# twoBandRepeater.net
KiCad netlist of a schematic drawn in EAGLE
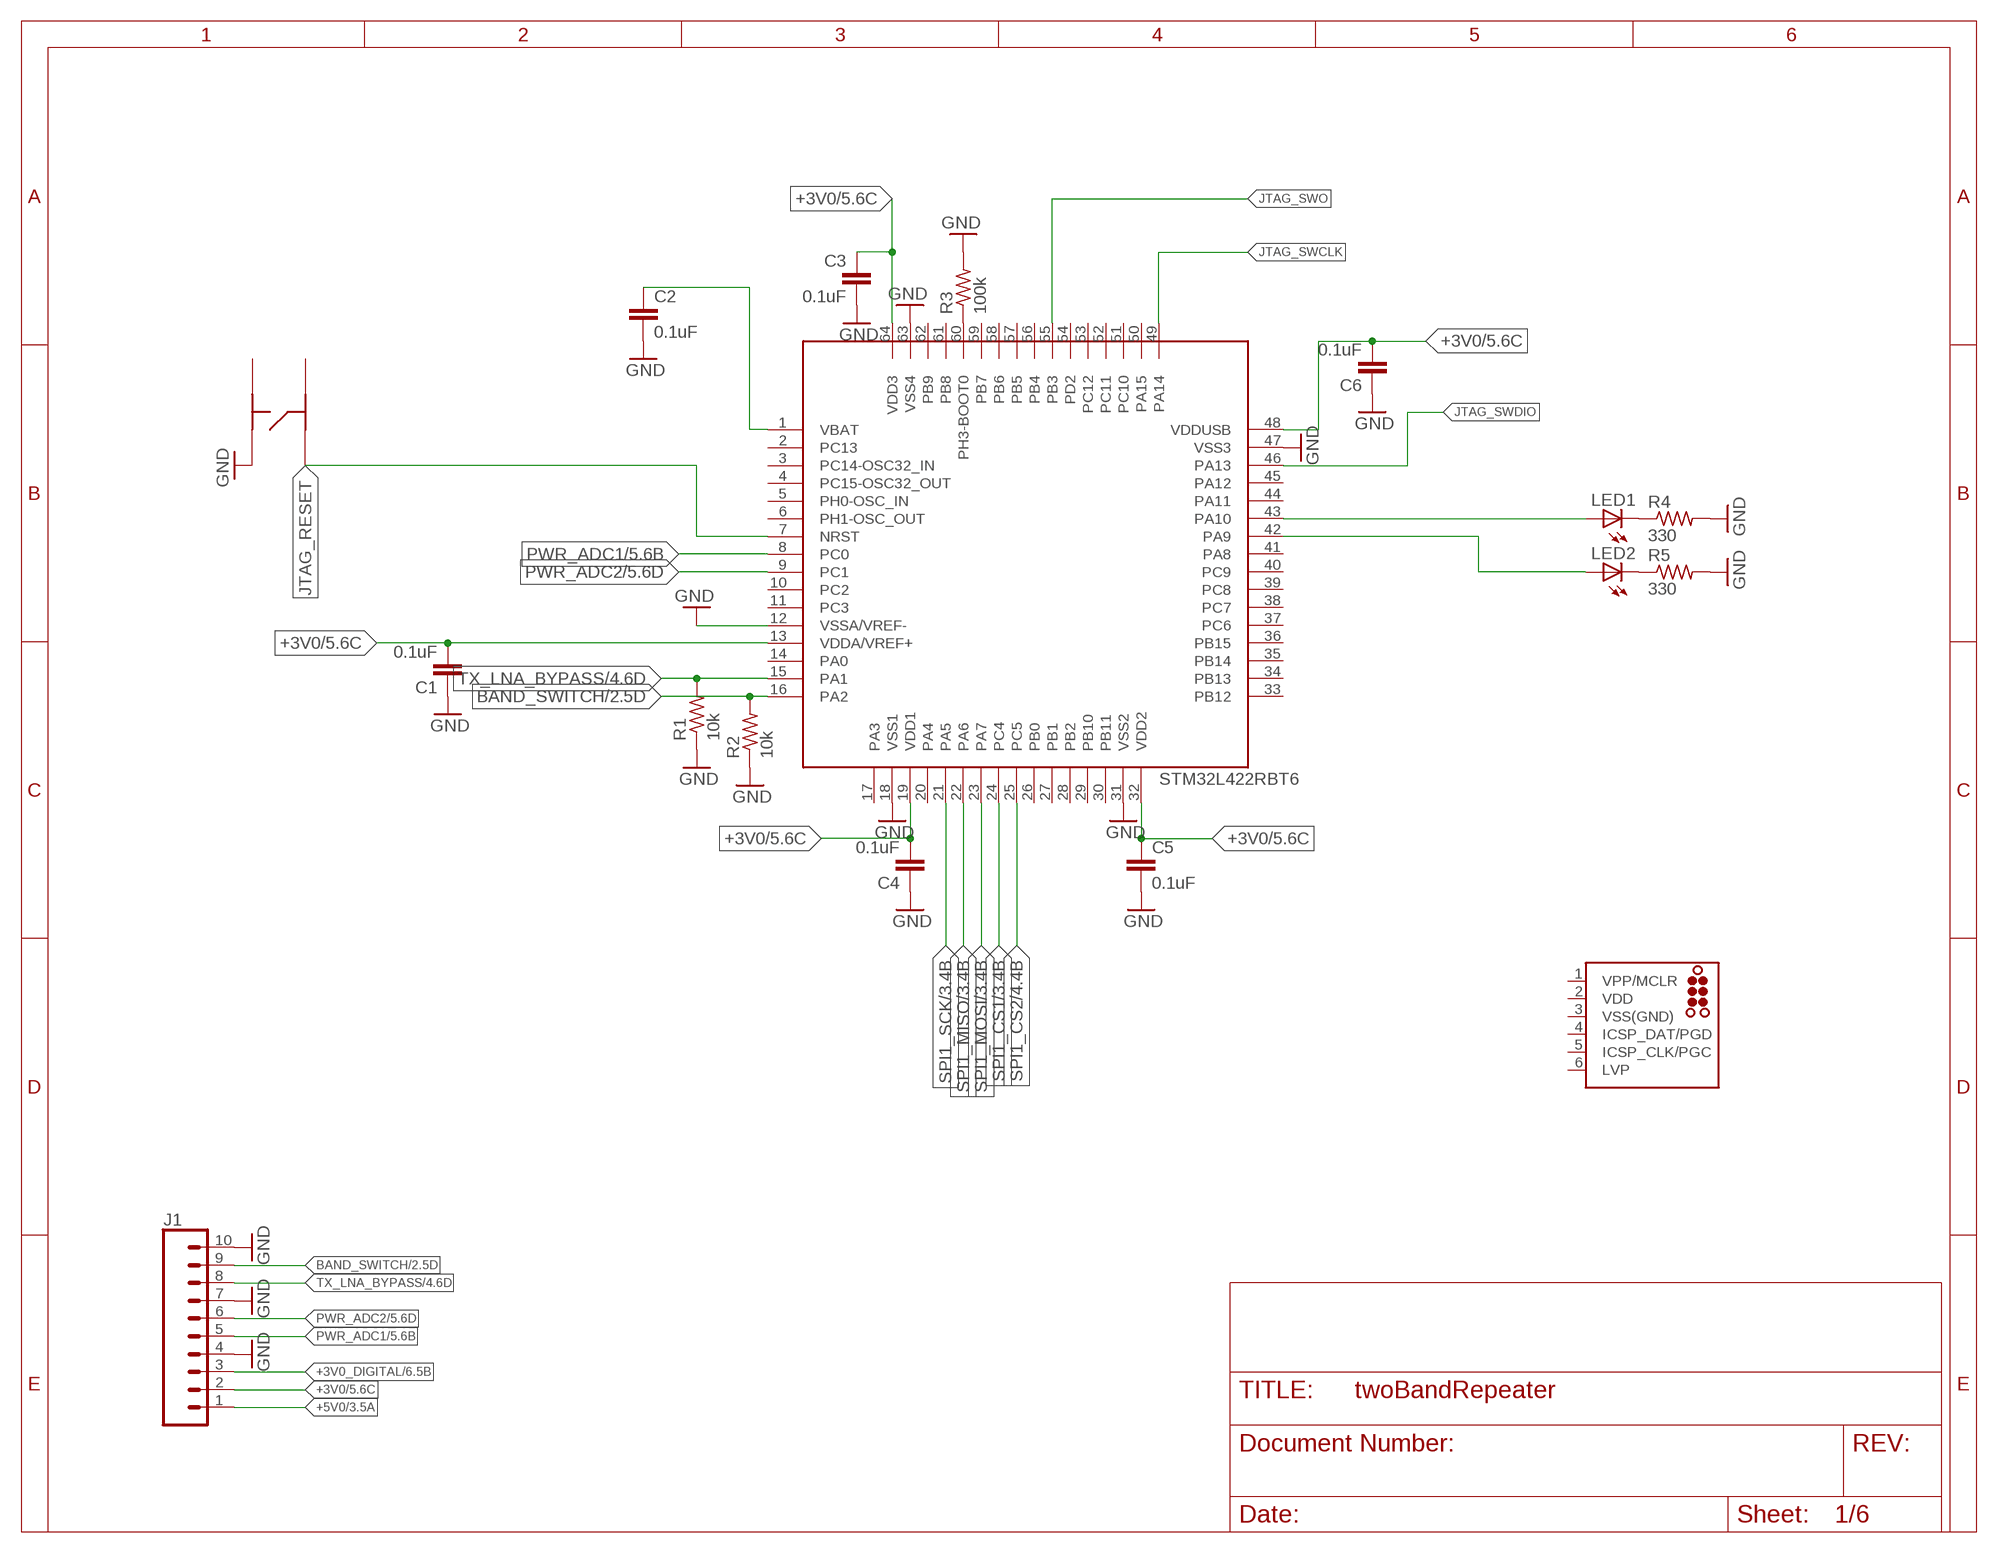
[diagram p0: schematic, sheet 1]
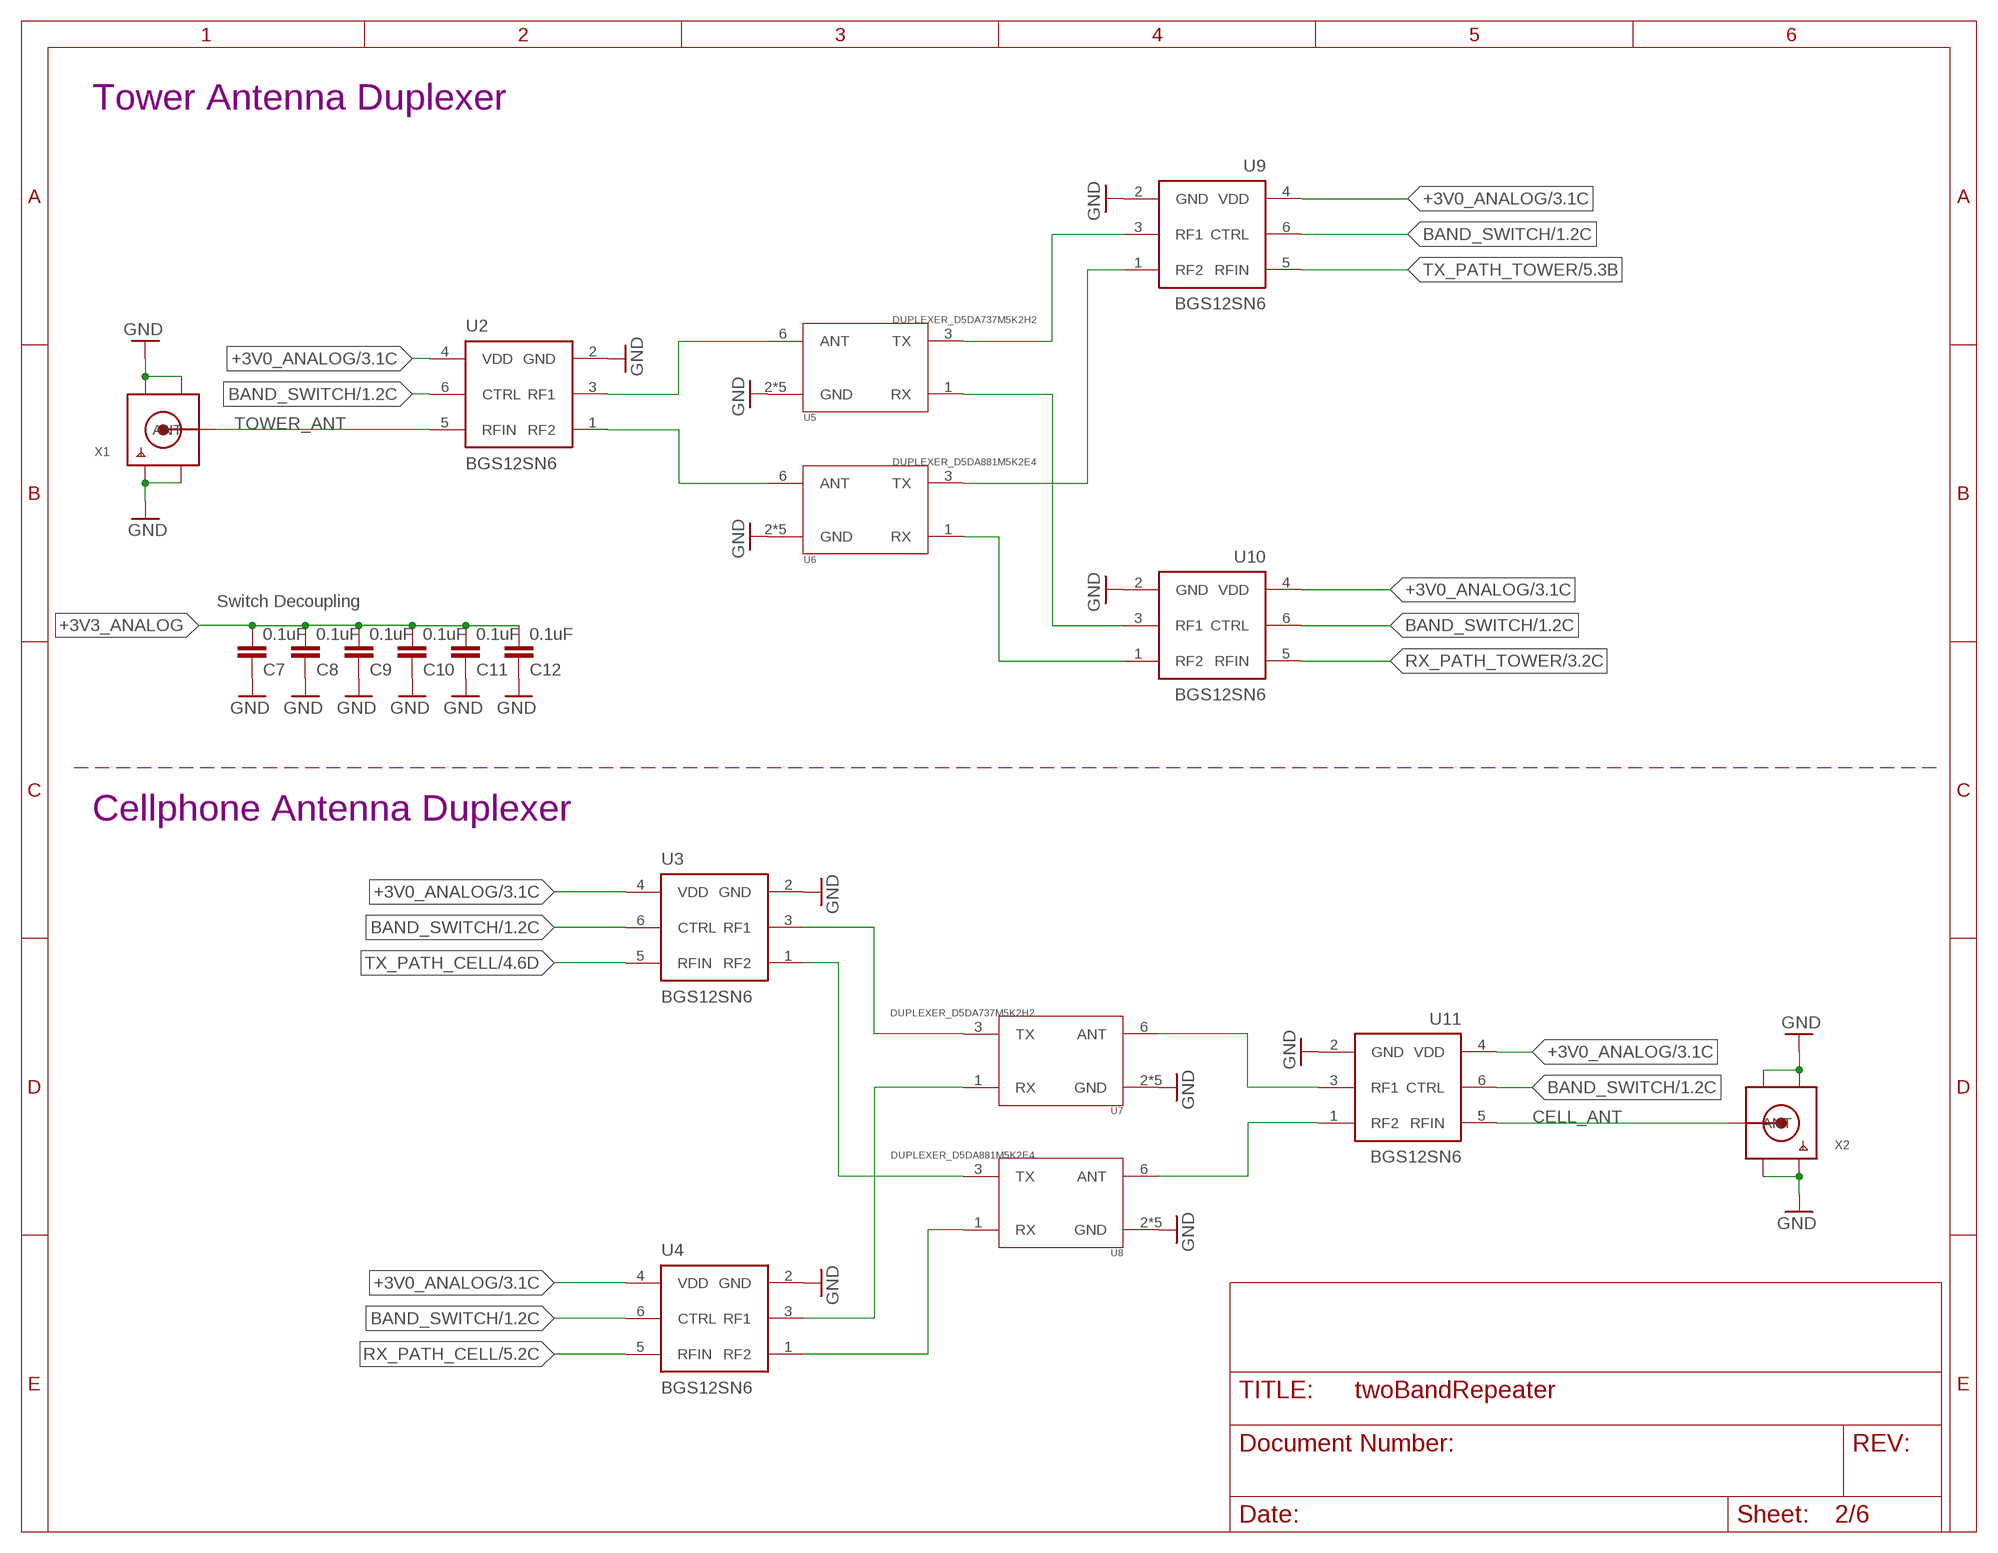
[diagram p1: schematic, sheet 2]
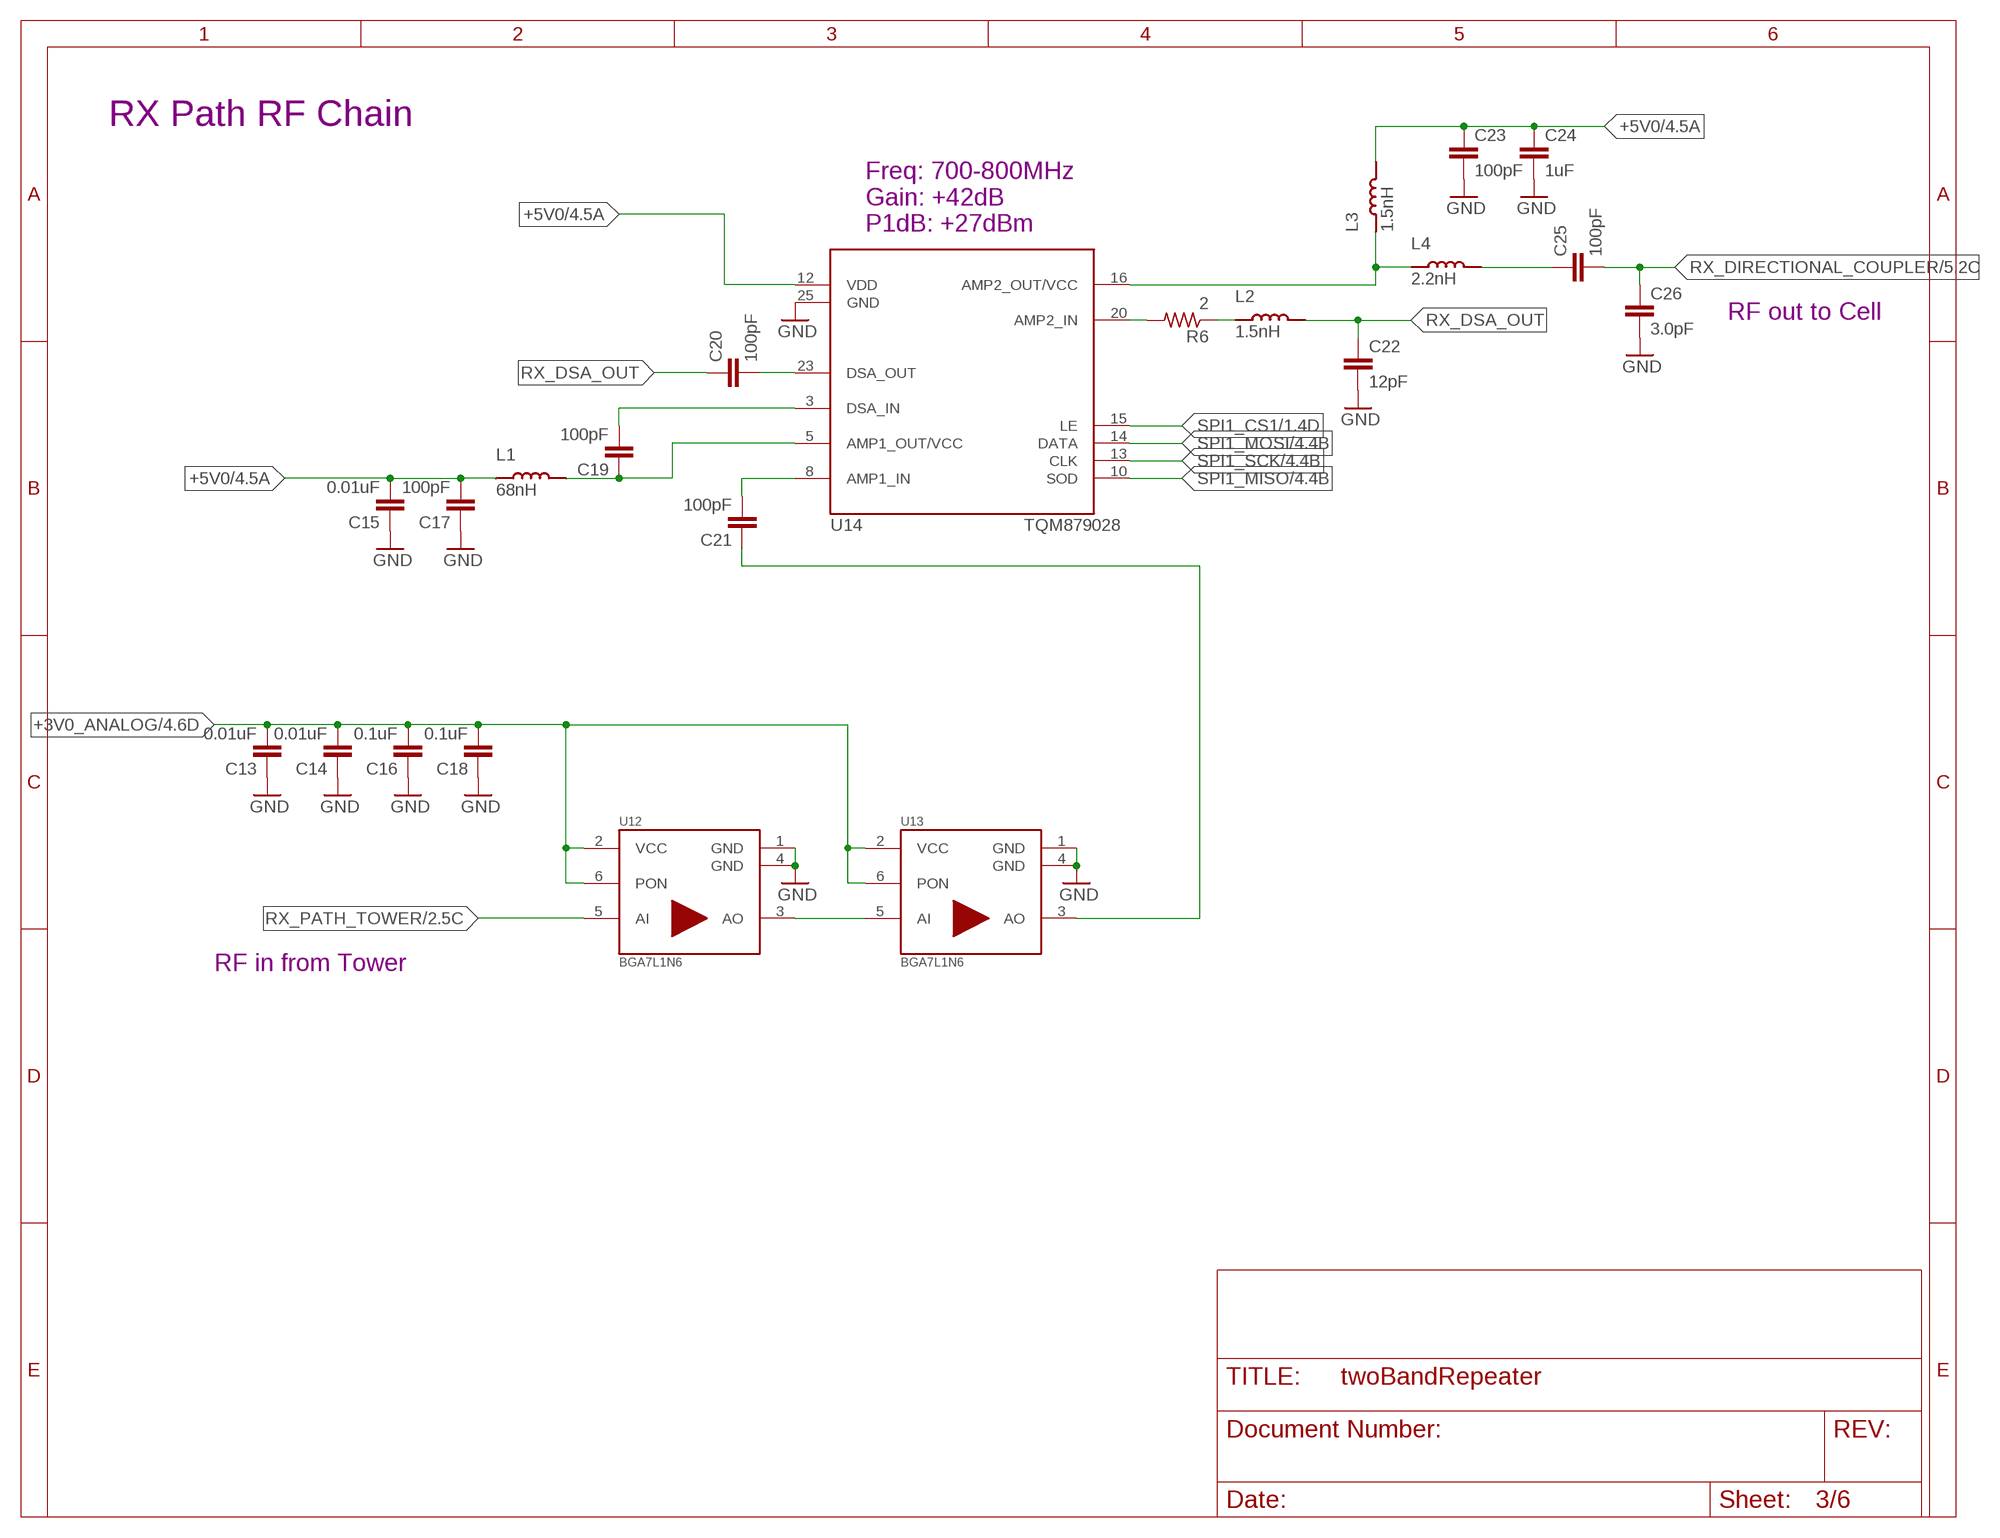
[diagram p2: schematic, sheet 3]
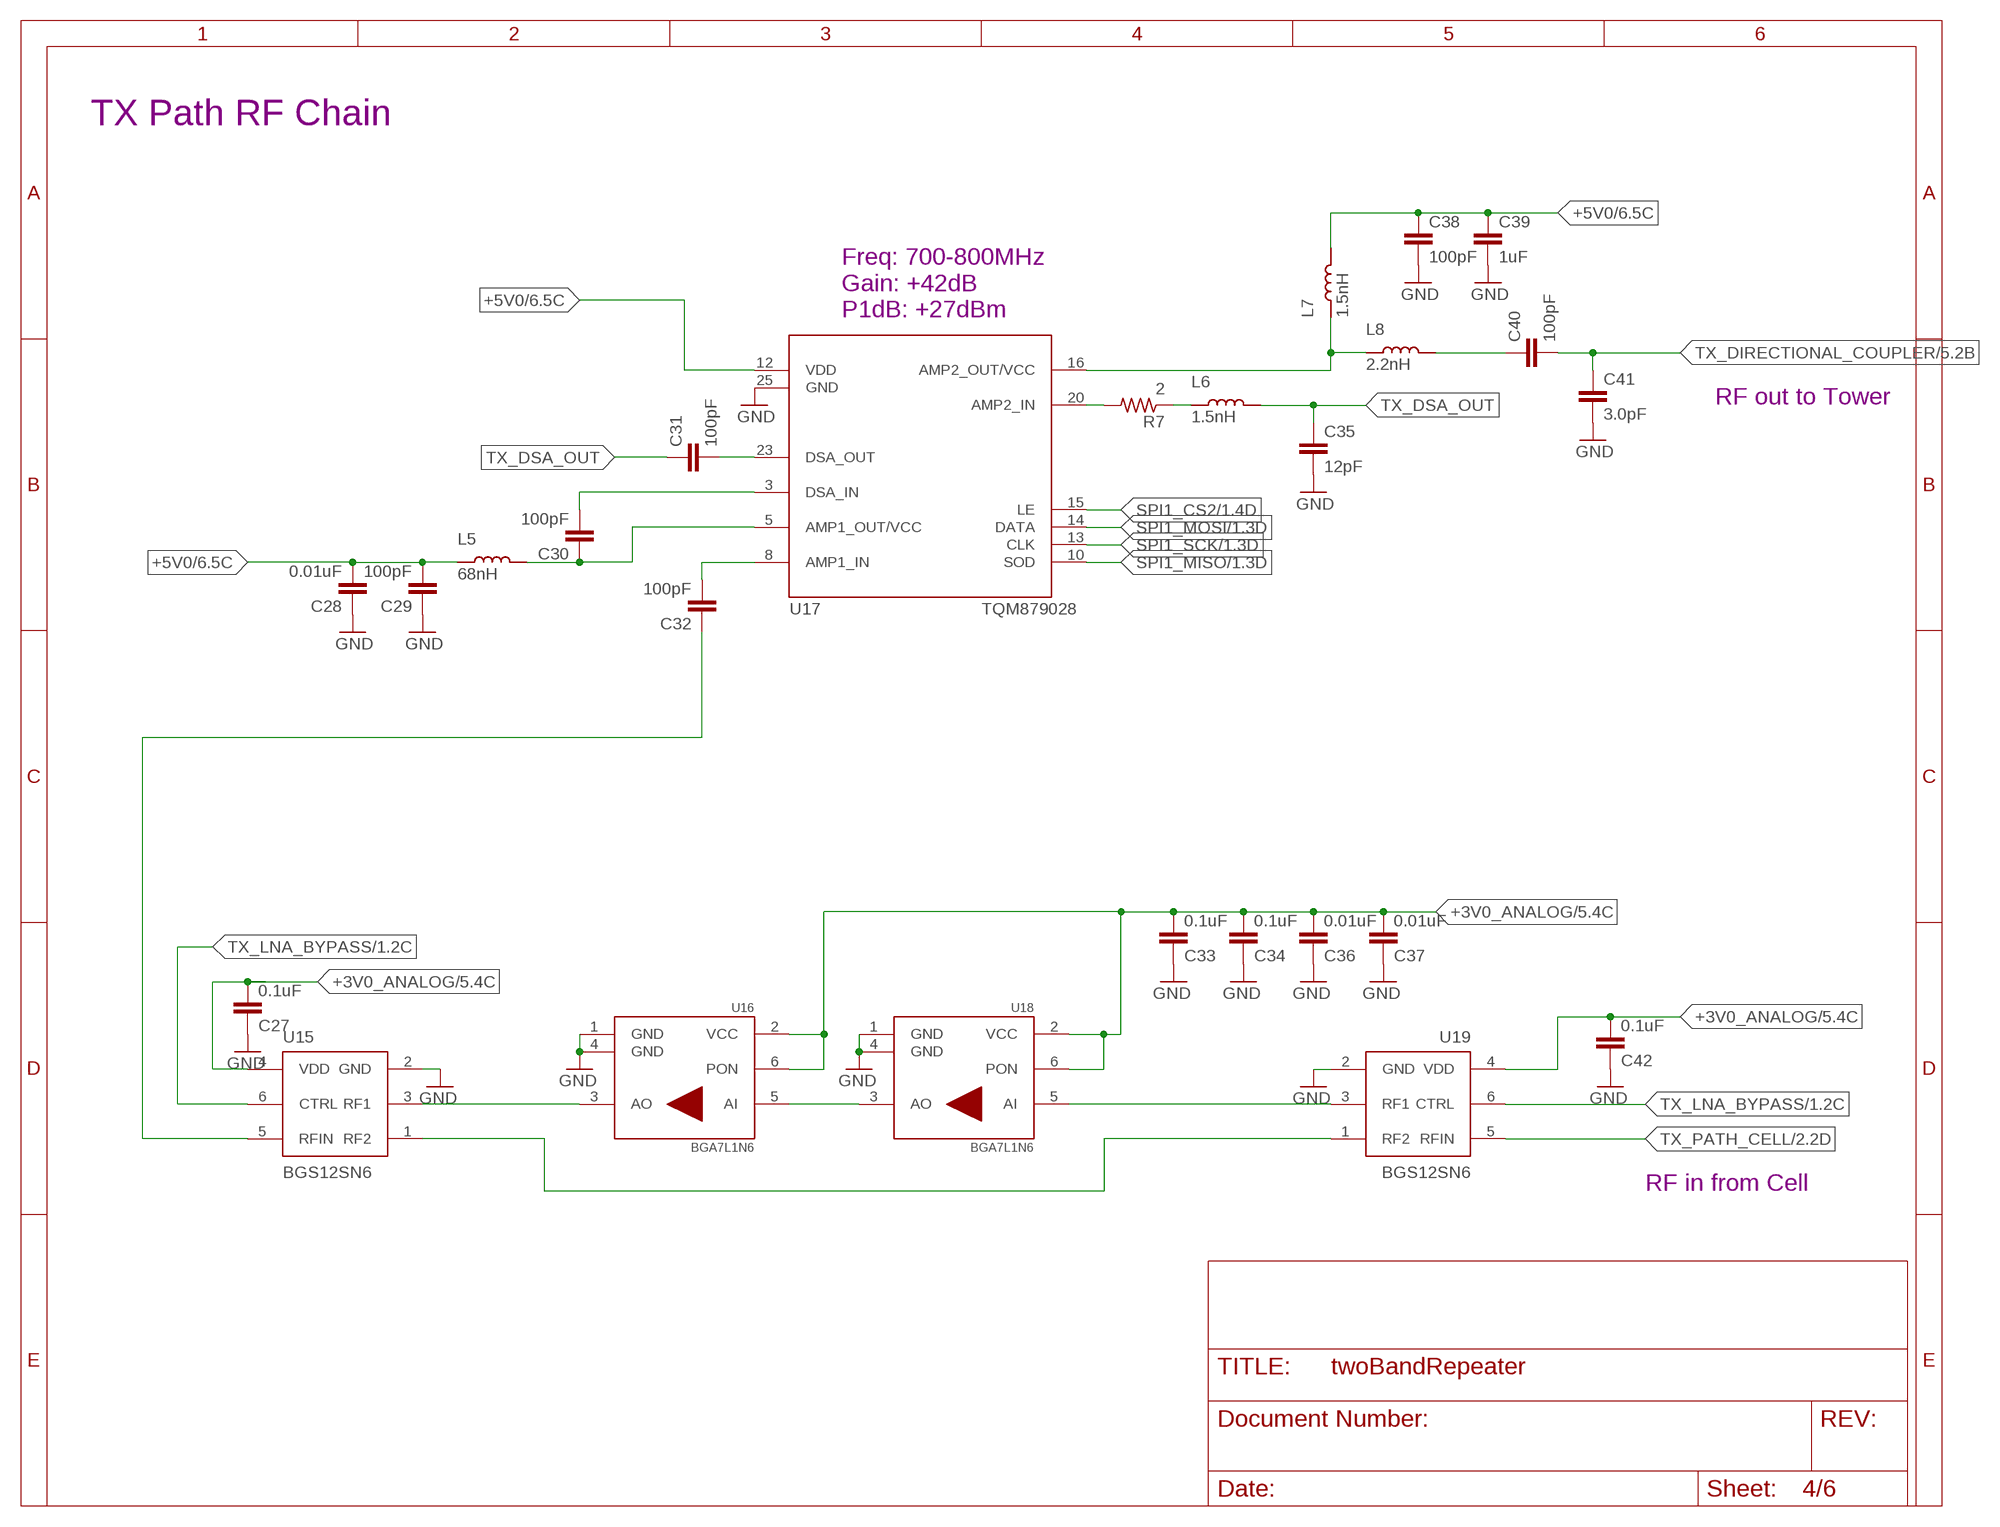
[diagram p3: schematic, sheet 4]
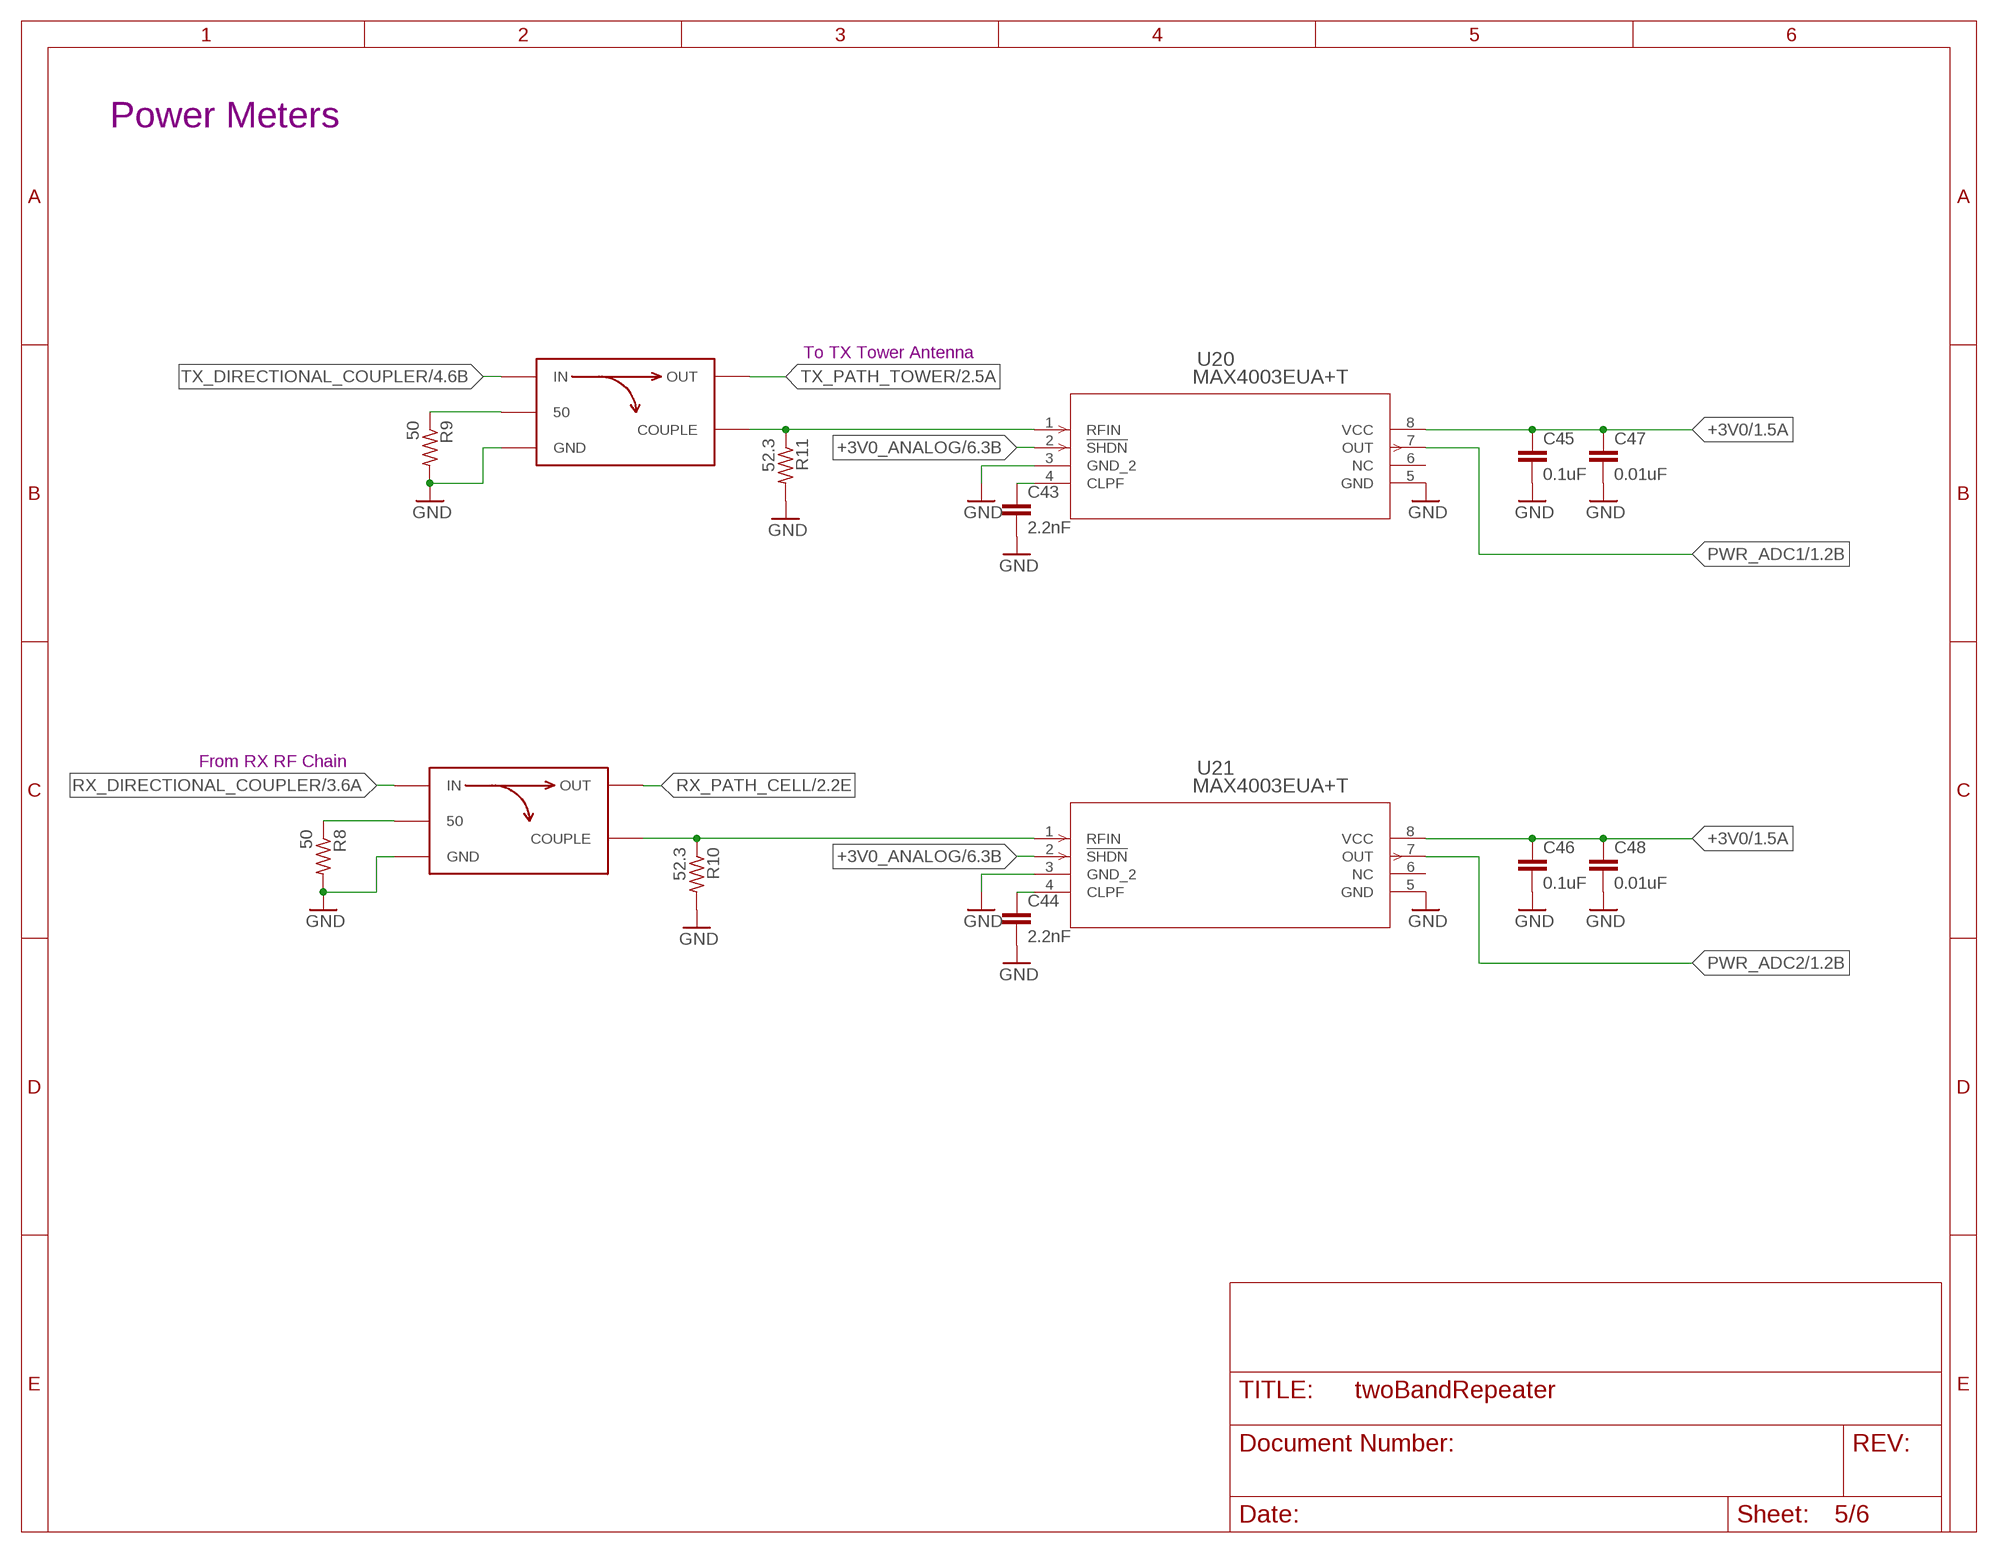
[diagram p4: schematic, sheet 5]
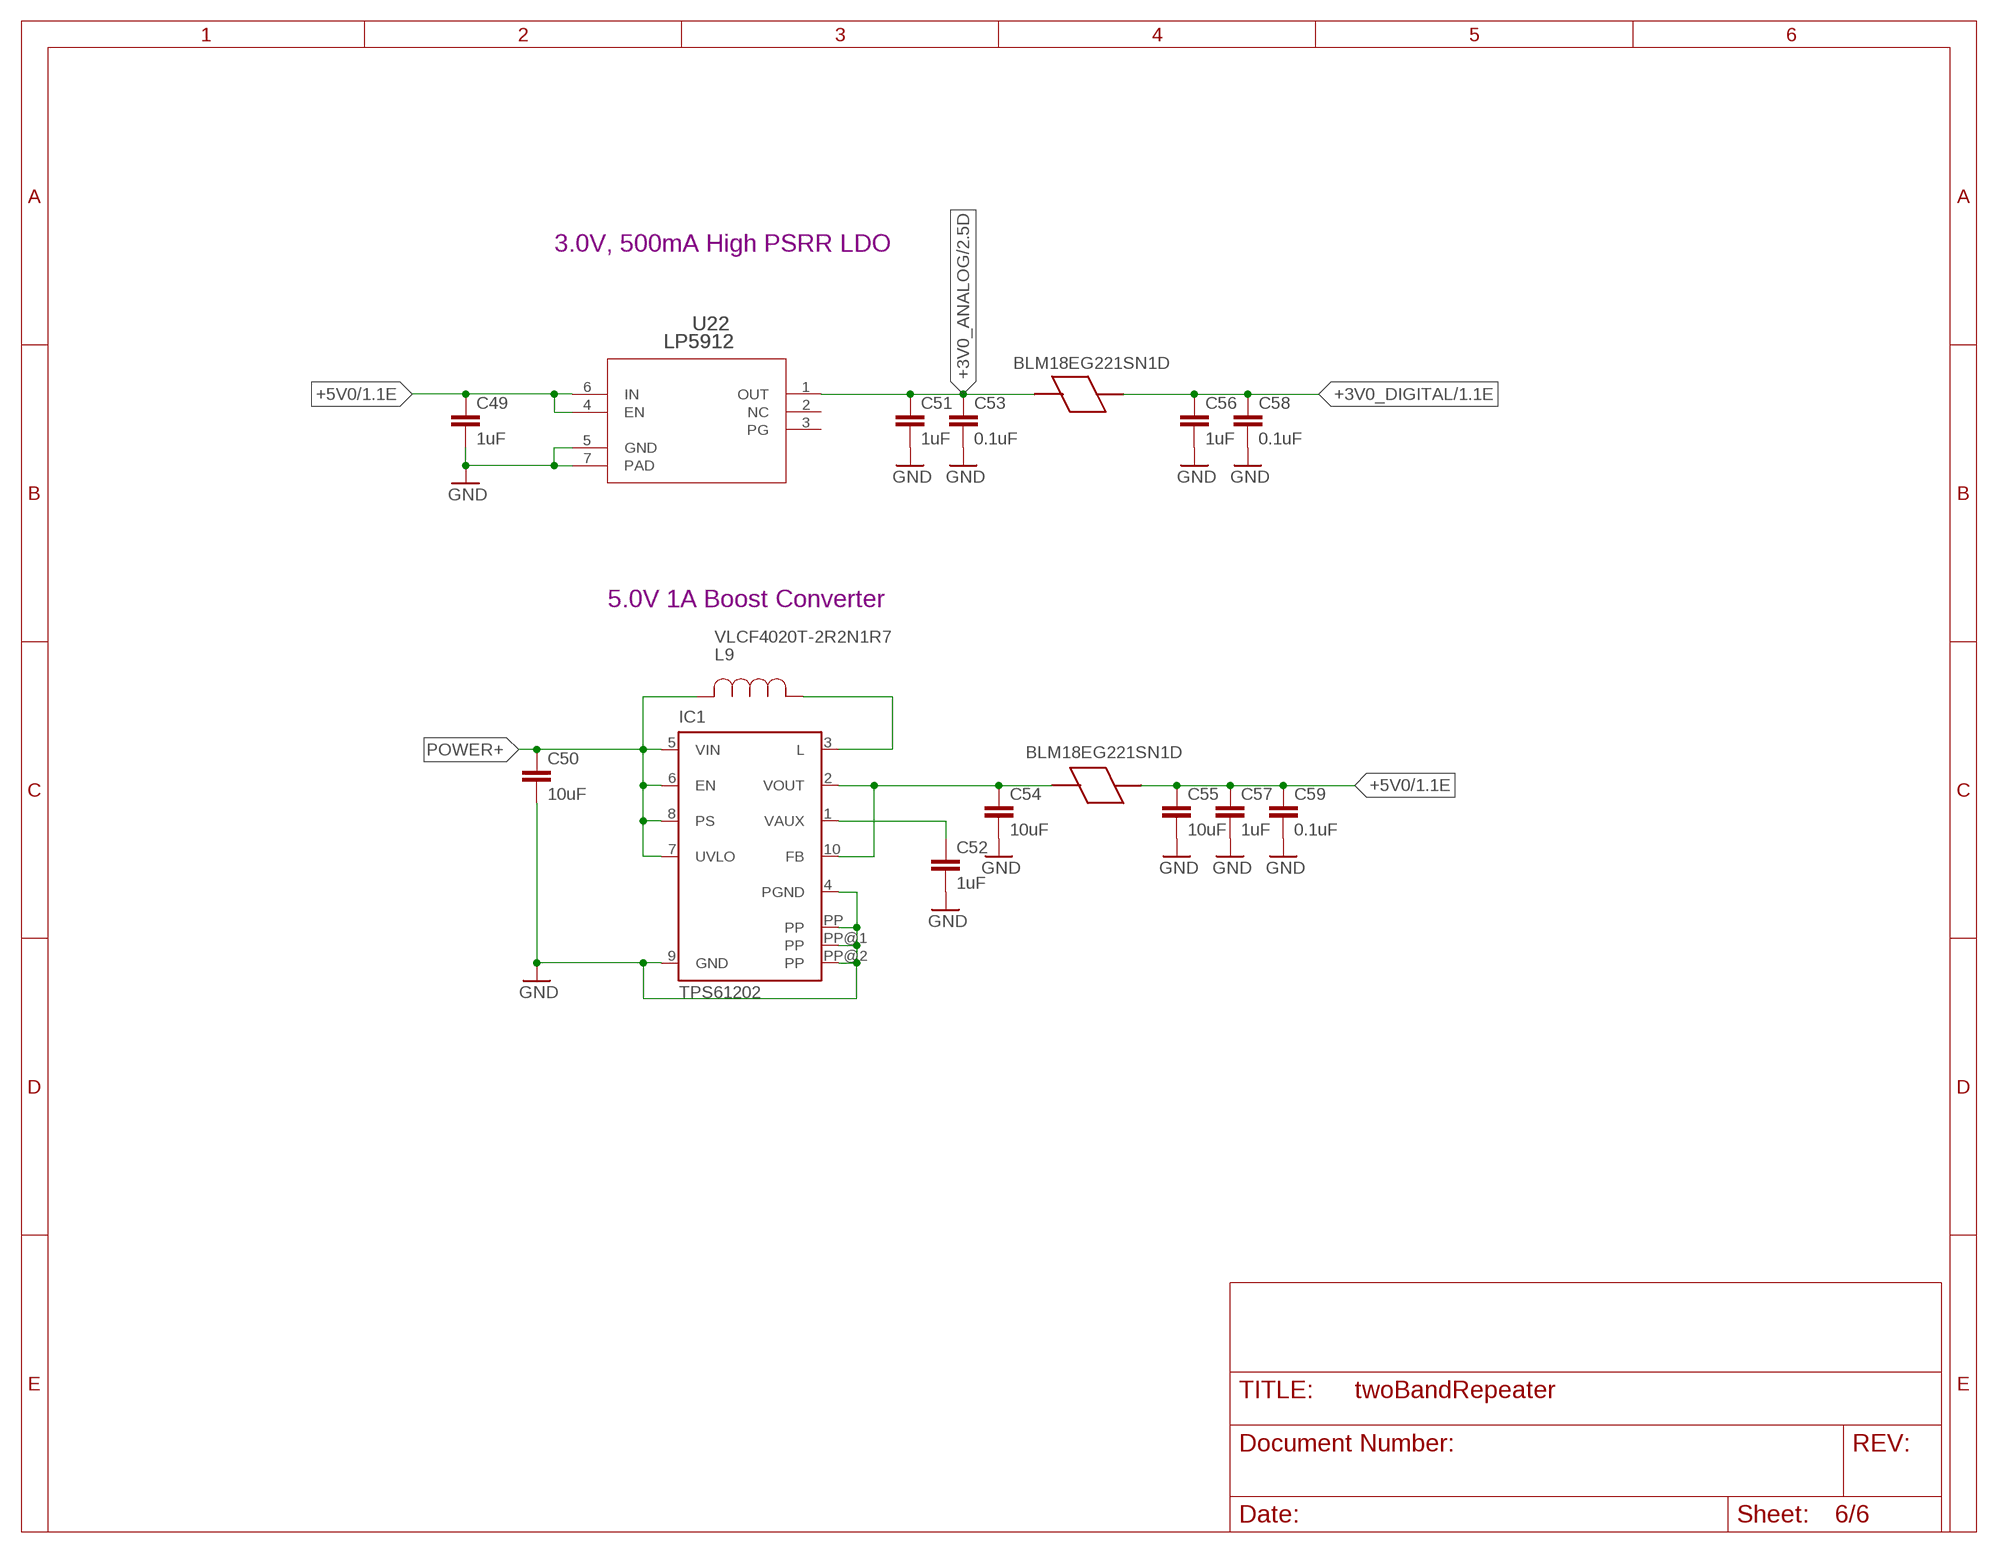
[diagram p5: schematic, sheet 6]

(export (version "E")
  (design (tool "Eeschema 10.0.6"))
  (components
    (comp (ref "C27")
      (value "0.1uF")
      (footprint "eagle-import:C0402")
      (libsource (lib "eagle-import") (part "C-EUC0402"))
    )
    (comp (ref "C28")
      (value "0.01uF")
      (footprint "eagle-import:C0402")
      (libsource (lib "eagle-import") (part "C-EUC0402"))
    )
    (comp (ref "C29")
      (value "100pF")
      (footprint "eagle-import:C0402")
      (libsource (lib "eagle-import") (part "C-EUC0402"))
    )
    (comp (ref "C30")
      (value "100pF")
      (footprint "eagle-import:C0402")
      (libsource (lib "eagle-import") (part "C-EUC0402"))
    )
    (comp (ref "C31")
      (value "100pF")
      (footprint "eagle-import:C0402")
      (libsource (lib "eagle-import") (part "C-EUC0402"))
    )
    (comp (ref "C32")
      (value "100pF")
      (footprint "eagle-import:C0402")
      (libsource (lib "eagle-import") (part "C-EUC0402"))
    )
    (comp (ref "C33")
      (value "0.1uF")
      (footprint "eagle-import:C0402")
      (libsource (lib "eagle-import") (part "C-EUC0402"))
    )
    (comp (ref "C34")
      (value "0.1uF")
      (footprint "eagle-import:C0402")
      (libsource (lib "eagle-import") (part "C-EUC0402"))
    )
    (comp (ref "C35")
      (value "12pF")
      (footprint "eagle-import:C0402")
      (libsource (lib "eagle-import") (part "C-EUC0402"))
    )
    (comp (ref "C36")
      (value "0.01uF")
      (footprint "eagle-import:C0402")
      (libsource (lib "eagle-import") (part "C-EUC0402"))
    )
    (comp (ref "C37")
      (value "0.01uF")
      (footprint "eagle-import:C0402")
      (libsource (lib "eagle-import") (part "C-EUC0402"))
    )
    (comp (ref "C38")
      (value "100pF")
      (footprint "eagle-import:C0402")
      (libsource (lib "eagle-import") (part "C-EUC0402"))
    )
    (comp (ref "C39")
      (value "1uF")
      (footprint "eagle-import:C0402")
      (libsource (lib "eagle-import") (part "C-EUC0402"))
    )
    (comp (ref "C40")
      (value "100pF")
      (footprint "eagle-import:C0402")
      (libsource (lib "eagle-import") (part "C-EUC0402"))
    )
    (comp (ref "C41")
      (value "3.0pF")
      (footprint "eagle-import:C0402")
      (libsource (lib "eagle-import") (part "C-EUC0402"))
    )
    (comp (ref "C42")
      (value "0.1uF")
      (footprint "eagle-import:C0402")
      (libsource (lib "eagle-import") (part "C-EUC0402"))
    )
    (comp (ref "L5")
      (value "68nH")
      (footprint "eagle-import:0402")
      (libsource (lib "eagle-import") (part "INDUCTOR0402"))
    )
    (comp (ref "L6")
      (value "1.5nH")
      (footprint "eagle-import:0402")
      (libsource (lib "eagle-import") (part "INDUCTOR0402"))
    )
    (comp (ref "L7")
      (value "1.5nH")
      (footprint "eagle-import:0402")
      (libsource (lib "eagle-import") (part "INDUCTOR0402"))
    )
    (comp (ref "L8")
      (value "2.2nH")
      (footprint "eagle-import:0402")
      (libsource (lib "eagle-import") (part "INDUCTOR0402"))
    )
    (comp (ref "R7")
      (value "2")
      (footprint "eagle-import:R0402")
      (libsource (lib "eagle-import") (part "R-US_R0402"))
    )
    (comp (ref "U15")
      (value "BGS12SN6")
      (footprint "eagle-import:INF-PG-TSNP-6-2")
      (libsource (lib "eagle-import") (part "BGS12SN6"))
    )
    (comp (ref "U16")
      (value "BGA7L1N6")
      (footprint "eagle-import:INF-PG-TSNP-6-2")
      (libsource (lib "eagle-import") (part "BGA7L1N6"))
    )
    (comp (ref "U17")
      (value "TQM879028")
      (footprint "eagle-import:QFN50P400X400X100-25T270N")
      (libsource (lib "eagle-import") (part "TQM879028"))
    )
    (comp (ref "U18")
      (value "BGA7L1N6")
      (footprint "eagle-import:INF-PG-TSNP-6-2")
      (libsource (lib "eagle-import") (part "BGA7L1N6"))
    )
    (comp (ref "U19")
      (value "BGS12SN6")
      (footprint "eagle-import:INF-PG-TSNP-6-2")
      (libsource (lib "eagle-import") (part "BGS12SN6"))
    )
    (comp (ref "C49")
      (value "1uF")
      (footprint "eagle-import:C0402")
      (libsource (lib "eagle-import") (part "C-EUC0402"))
    )
    (comp (ref "C50")
      (value "10uF")
      (footprint "eagle-import:C0805")
      (libsource (lib "eagle-import") (part "C-EUC0805"))
    )
    (comp (ref "C51")
      (value "1uF")
      (footprint "eagle-import:C0402")
      (libsource (lib "eagle-import") (part "C-EUC0402"))
    )
    (comp (ref "C52")
      (value "1uF")
      (footprint "eagle-import:C0402")
      (libsource (lib "eagle-import") (part "C-EUC0402"))
    )
    (comp (ref "C53")
      (value "0.1uF")
      (footprint "eagle-import:C0402")
      (libsource (lib "eagle-import") (part "C-EUC0402"))
    )
    (comp (ref "C54")
      (value "10uF")
      (footprint "eagle-import:C0805")
      (libsource (lib "eagle-import") (part "C-EUC0805"))
    )
    (comp (ref "C55")
      (value "10uF")
      (footprint "eagle-import:C0805")
      (libsource (lib "eagle-import") (part "C-EUC0805"))
    )
    (comp (ref "C56")
      (value "1uF")
      (footprint "eagle-import:C0402")
      (libsource (lib "eagle-import") (part "C-EUC0402"))
    )
    (comp (ref "C57")
      (value "1uF")
      (footprint "eagle-import:C0402")
      (libsource (lib "eagle-import") (part "C-EUC0402"))
    )
    (comp (ref "C58")
      (value "0.1uF")
      (footprint "eagle-import:C0402")
      (libsource (lib "eagle-import") (part "C-EUC0402"))
    )
    (comp (ref "C59")
      (value "0.1uF")
      (footprint "eagle-import:C0402")
      (libsource (lib "eagle-import") (part "C-EUC0402"))
    )
    (comp (ref "IC1")
      (value "TPS61202")
      (footprint "eagle-import:S-PDSO-N10")
      (fields (field (name "MPN") "TPS61202DRCR"))
      (libsource (lib "eagle-import") (part "TPS61202"))
    )
    (comp (ref "L9")
      (value "VLCF4020T-2R2N1R7")
      (footprint "eagle-import:IND_4028")
      (libsource (lib "eagle-import") (part "VLCF4020T-2R2N1R7"))
    )
    (comp (ref "L10")
      (value "BLM18EG221SN1D")
      (footprint "eagle-import:IND_BLM18_0603")
      (fields (field (name "COPYRIGHT") "Copyright C 2015 Accelerated Designs. All rights reserved"))
      (libsource (lib "eagle-import") (part "BLM18EG221SN1D"))
    )
    (comp (ref "L11")
      (value "BLM18EG221SN1D")
      (footprint "eagle-import:IND_BLM18_0603")
      (fields (field (name "COPYRIGHT") "Copyright C 2015 Accelerated Designs. All rights reserved"))
      (libsource (lib "eagle-import") (part "BLM18EG221SN1D"))
    )
    (comp (ref "U22")
      (value "LP5912")
      (footprint "eagle-import:DRV0006A")
      (libsource (lib "eagle-import") (part "LP5912"))
    )
    (comp (ref "C13")
      (value "0.01uF")
      (footprint "eagle-import:C0402")
      (libsource (lib "eagle-import") (part "C-EUC0402"))
    )
    (comp (ref "C14")
      (value "0.01uF")
      (footprint "eagle-import:C0402")
      (libsource (lib "eagle-import") (part "C-EUC0402"))
    )
    (comp (ref "C15")
      (value "0.01uF")
      (footprint "eagle-import:C0402")
      (libsource (lib "eagle-import") (part "C-EUC0402"))
    )
    (comp (ref "C16")
      (value "0.1uF")
      (footprint "eagle-import:C0402")
      (libsource (lib "eagle-import") (part "C-EUC0402"))
    )
    (comp (ref "C17")
      (value "100pF")
      (footprint "eagle-import:C0402")
      (libsource (lib "eagle-import") (part "C-EUC0402"))
    )
    (comp (ref "C18")
      (value "0.1uF")
      (footprint "eagle-import:C0402")
      (libsource (lib "eagle-import") (part "C-EUC0402"))
    )
    (comp (ref "C19")
      (value "100pF")
      (footprint "eagle-import:C0402")
      (libsource (lib "eagle-import") (part "C-EUC0402"))
    )
    (comp (ref "C20")
      (value "100pF")
      (footprint "eagle-import:C0402")
      (libsource (lib "eagle-import") (part "C-EUC0402"))
    )
    (comp (ref "C21")
      (value "100pF")
      (footprint "eagle-import:C0402")
      (libsource (lib "eagle-import") (part "C-EUC0402"))
    )
    (comp (ref "C22")
      (value "12pF")
      (footprint "eagle-import:C0402")
      (libsource (lib "eagle-import") (part "C-EUC0402"))
    )
    (comp (ref "C23")
      (value "100pF")
      (footprint "eagle-import:C0402")
      (libsource (lib "eagle-import") (part "C-EUC0402"))
    )
    (comp (ref "C24")
      (value "1uF")
      (footprint "eagle-import:C0402")
      (libsource (lib "eagle-import") (part "C-EUC0402"))
    )
    (comp (ref "C25")
      (value "100pF")
      (footprint "eagle-import:C0402")
      (libsource (lib "eagle-import") (part "C-EUC0402"))
    )
    (comp (ref "C26")
      (value "3.0pF")
      (footprint "eagle-import:C0402")
      (libsource (lib "eagle-import") (part "C-EUC0402"))
    )
    (comp (ref "L1")
      (value "68nH")
      (footprint "eagle-import:0402")
      (libsource (lib "eagle-import") (part "INDUCTOR0402"))
    )
    (comp (ref "L2")
      (value "1.5nH")
      (footprint "eagle-import:0402")
      (libsource (lib "eagle-import") (part "INDUCTOR0402"))
    )
    (comp (ref "L3")
      (value "1.5nH")
      (footprint "eagle-import:0402")
      (libsource (lib "eagle-import") (part "INDUCTOR0402"))
    )
    (comp (ref "L4")
      (value "2.2nH")
      (footprint "eagle-import:0402")
      (libsource (lib "eagle-import") (part "INDUCTOR0402"))
    )
    (comp (ref "R6")
      (value "2")
      (footprint "eagle-import:R0402")
      (libsource (lib "eagle-import") (part "R-US_R0402"))
    )
    (comp (ref "U12")
      (value "BGA7L1N6")
      (footprint "eagle-import:INF-PG-TSNP-6-2")
      (libsource (lib "eagle-import") (part "BGA7L1N6"))
    )
    (comp (ref "U13")
      (value "BGA7L1N6")
      (footprint "eagle-import:INF-PG-TSNP-6-2")
      (libsource (lib "eagle-import") (part "BGA7L1N6"))
    )
    (comp (ref "U14")
      (value "TQM879028")
      (footprint "eagle-import:QFN50P400X400X100-25T270N")
      (libsource (lib "eagle-import") (part "TQM879028"))
    )
    (comp (ref "C43")
      (value "2.2nF")
      (footprint "eagle-import:C0402")
      (libsource (lib "eagle-import") (part "C-EUC0402"))
    )
    (comp (ref "C44")
      (value "2.2nF")
      (footprint "eagle-import:C0402")
      (libsource (lib "eagle-import") (part "C-EUC0402"))
    )
    (comp (ref "C45")
      (value "0.1uF")
      (footprint "eagle-import:C0402")
      (libsource (lib "eagle-import") (part "C-EUC0402"))
    )
    (comp (ref "C46")
      (value "0.1uF")
      (footprint "eagle-import:C0402")
      (libsource (lib "eagle-import") (part "C-EUC0402"))
    )
    (comp (ref "C47")
      (value "0.01uF")
      (footprint "eagle-import:C0402")
      (libsource (lib "eagle-import") (part "C-EUC0402"))
    )
    (comp (ref "C48")
      (value "0.01uF")
      (footprint "eagle-import:C0402")
      (libsource (lib "eagle-import") (part "C-EUC0402"))
    )
    (comp (ref "HY1")
      (value "HHM22152A2")
      (footprint "eagle-import:HHM22152A2")
      (libsource (lib "eagle-import") (part "HHM22152A2"))
    )
    (comp (ref "HY2")
      (value "HHM22152A2")
      (footprint "eagle-import:HHM22152A2")
      (libsource (lib "eagle-import") (part "HHM22152A2"))
    )
    (comp (ref "R8")
      (value "50")
      (footprint "eagle-import:R0402")
      (libsource (lib "eagle-import") (part "R-US_R0402"))
    )
    (comp (ref "R9")
      (value "50")
      (footprint "eagle-import:R0402")
      (libsource (lib "eagle-import") (part "R-US_R0402"))
    )
    (comp (ref "R10")
      (value "52.3")
      (footprint "eagle-import:R0402")
      (libsource (lib "eagle-import") (part "R-US_R0402"))
    )
    (comp (ref "R11")
      (value "52.3")
      (footprint "eagle-import:R0402")
      (libsource (lib "eagle-import") (part "R-US_R0402"))
    )
    (comp (ref "U20")
      (value "MAX4003EUA+T")
      (footprint "eagle-import:21-0036K")
      (fields (field (name "MANUFACTURER_PART_NUMBER") "max4003eua+T"))
      (libsource (lib "eagle-import") (part "MAX4003EUA+T"))
    )
    (comp (ref "U21")
      (value "MAX4003EUA+T")
      (footprint "eagle-import:21-0036K")
      (fields (field (name "MANUFACTURER_PART_NUMBER") "max4003eua+T"))
      (libsource (lib "eagle-import") (part "MAX4003EUA+T"))
    )
    (comp (ref "C1")
      (value "0.1uF")
      (footprint "eagle-import:C0402")
      (libsource (lib "eagle-import") (part "C-EUC0402"))
    )
    (comp (ref "C2")
      (value "0.1uF")
      (footprint "eagle-import:C0402")
      (libsource (lib "eagle-import") (part "C-EUC0402"))
    )
    (comp (ref "C3")
      (value "0.1uF")
      (footprint "eagle-import:C0402")
      (libsource (lib "eagle-import") (part "C-EUC0402"))
    )
    (comp (ref "C4")
      (value "0.1uF")
      (footprint "eagle-import:C0402")
      (libsource (lib "eagle-import") (part "C-EUC0402"))
    )
    (comp (ref "C5")
      (value "0.1uF")
      (footprint "eagle-import:C0402")
      (libsource (lib "eagle-import") (part "C-EUC0402"))
    )
    (comp (ref "C6")
      (value "0.1uF")
      (footprint "eagle-import:C0402")
      (libsource (lib "eagle-import") (part "C-EUC0402"))
    )
    (comp (ref "J1")
      (value "CONN_10\"")
      (footprint "eagle-import:1X10")
      (libsource (lib "eagle-import") (part "CONN_10{dblquote}"))
    )
    (comp (ref "J2")
      (value "TC2030-MCP")
      (footprint "eagle-import:TC2030-MCP")
      (libsource (lib "eagle-import") (part "TC2030-MCP"))
    )
    (comp (ref "LED1")
      (value "LEDCHIP-LED0603")
      (footprint "eagle-import:CHIP-LED0603")
      (libsource (lib "eagle-import") (part "LEDCHIP-LED0603"))
    )
    (comp (ref "LED2")
      (value "LEDCHIP-LED0603")
      (footprint "eagle-import:CHIP-LED0603")
      (libsource (lib "eagle-import") (part "LEDCHIP-LED0603"))
    )
    (comp (ref "R1")
      (value "10k")
      (footprint "eagle-import:R0402")
      (libsource (lib "eagle-import") (part "R-US_R0402"))
    )
    (comp (ref "R2")
      (value "10k")
      (footprint "eagle-import:R0402")
      (libsource (lib "eagle-import") (part "R-US_R0402"))
    )
    (comp (ref "R3")
      (value "100k")
      (footprint "eagle-import:R0402")
      (libsource (lib "eagle-import") (part "R-US_R0402"))
    )
    (comp (ref "R4")
      (value "330")
      (footprint "eagle-import:R0402")
      (libsource (lib "eagle-import") (part "R-US_R0402"))
    )
    (comp (ref "R5")
      (value "330")
      (footprint "eagle-import:R0402")
      (libsource (lib "eagle-import") (part "R-US_R0402"))
    )
    (comp (ref "S1")
      (value "KMR731NG")
      (footprint "eagle-import:KMR731NG")
      (libsource (lib "eagle-import") (part "KMR731NG"))
    )
    (comp (ref "U1")
      (value "STM32L422RBT6")
      (footprint "eagle-import:QFP50P1200X1200X160-64")
      (libsource (lib "eagle-import") (part "STM32L422RBT6"))
    )
    (comp (ref "C7")
      (value "0.1uF")
      (footprint "eagle-import:C0402")
      (libsource (lib "eagle-import") (part "C-EUC0402"))
    )
    (comp (ref "C8")
      (value "0.1uF")
      (footprint "eagle-import:C0402")
      (libsource (lib "eagle-import") (part "C-EUC0402"))
    )
    (comp (ref "C9")
      (value "0.1uF")
      (footprint "eagle-import:C0402")
      (libsource (lib "eagle-import") (part "C-EUC0402"))
    )
    (comp (ref "C10")
      (value "0.1uF")
      (footprint "eagle-import:C0402")
      (libsource (lib "eagle-import") (part "C-EUC0402"))
    )
    (comp (ref "C11")
      (value "0.1uF")
      (footprint "eagle-import:C0402")
      (libsource (lib "eagle-import") (part "C-EUC0402"))
    )
    (comp (ref "C12")
      (value "0.1uF")
      (footprint "eagle-import:C0402")
      (libsource (lib "eagle-import") (part "C-EUC0402"))
    )
    (comp (ref "U2")
      (value "BGS12SN6")
      (footprint "eagle-import:INF-PG-TSNP-6-2")
      (libsource (lib "eagle-import") (part "BGS12SN6"))
    )
    (comp (ref "U3")
      (value "BGS12SN6")
      (footprint "eagle-import:INF-PG-TSNP-6-2")
      (libsource (lib "eagle-import") (part "BGS12SN6"))
    )
    (comp (ref "U4")
      (value "BGS12SN6")
      (footprint "eagle-import:INF-PG-TSNP-6-2")
      (libsource (lib "eagle-import") (part "BGS12SN6"))
    )
    (comp (ref "U5")
      (value "DUPLEXER_D5DA737M5K2H2")
      (footprint "eagle-import:TAIYO_YUDEN_DUPLEX_1.8X1.4")
      (libsource (lib "eagle-import") (part "DUPLEXER_D5DA737M5K2H2"))
    )
    (comp (ref "U6")
      (value "DUPLEXER_D5DA881M5K2E4")
      (footprint "eagle-import:TAIYO_YUDEN_DUPLEX_1.8X1.4")
      (libsource (lib "eagle-import") (part "DUPLEXER_D5DA881M5K2E4"))
    )
    (comp (ref "U7")
      (value "DUPLEXER_D5DA737M5K2H2")
      (footprint "eagle-import:TAIYO_YUDEN_DUPLEX_1.8X1.4")
      (libsource (lib "eagle-import") (part "DUPLEXER_D5DA737M5K2H2"))
    )
    (comp (ref "U8")
      (value "DUPLEXER_D5DA881M5K2E4")
      (footprint "eagle-import:TAIYO_YUDEN_DUPLEX_1.8X1.4")
      (libsource (lib "eagle-import") (part "DUPLEXER_D5DA881M5K2E4"))
    )
    (comp (ref "U9")
      (value "BGS12SN6")
      (footprint "eagle-import:INF-PG-TSNP-6-2")
      (libsource (lib "eagle-import") (part "BGS12SN6"))
    )
    (comp (ref "U10")
      (value "BGS12SN6")
      (footprint "eagle-import:INF-PG-TSNP-6-2")
      (libsource (lib "eagle-import") (part "BGS12SN6"))
    )
    (comp (ref "U11")
      (value "BGS12SN6")
      (footprint "eagle-import:INF-PG-TSNP-6-2")
      (libsource (lib "eagle-import") (part "BGS12SN6"))
    )
    (comp (ref "X1")
      (value "SMACONNECTORSMA_DIP")
      (footprint "eagle-import:SMA_DIP")
      (libsource (lib "eagle-import") (part "SMACONNECTORSMA_DIP"))
    )
    (comp (ref "X2")
      (value "SMACONNECTORSMA_DIP")
      (footprint "eagle-import:SMA_DIP")
      (libsource (lib "eagle-import") (part "SMACONNECTORSMA_DIP"))
    )
  )
  (nets
    (net (code "1") (name "+3V0") (class "Default")
      (node (ref "C1") (pin "2") (pinfunction "2_2") (pintype "passive"))
      (node (ref "C3") (pin "1") (pinfunction "1_1") (pintype "passive"))
      (node (ref "C4") (pin "2") (pinfunction "2_2") (pintype "passive"))
      (node (ref "C45") (pin "1") (pinfunction "1_1") (pintype "passive"))
      (node (ref "C46") (pin "1") (pinfunction "1_1") (pintype "passive"))
      (node (ref "C47") (pin "1") (pinfunction "1_1") (pintype "passive"))
      (node (ref "C48") (pin "1") (pinfunction "1_1") (pintype "passive"))
      (node (ref "C5") (pin "1") (pinfunction "1_1") (pintype "passive"))
      (node (ref "C6") (pin "2") (pinfunction "2_2") (pintype "passive"))
      (node (ref "J1") (pin "2") (pinfunction "2_2") (pintype "passive"))
      (node (ref "U1") (pin "13") (pinfunction "VDDA/VREF+_13") (pintype "bidirectional"))
      (node (ref "U1") (pin "19") (pinfunction "VDD1_19") (pintype "bidirectional"))
      (node (ref "U1") (pin "32") (pinfunction "VDD2_32") (pintype "bidirectional"))
      (node (ref "U1") (pin "48") (pinfunction "VDDUSB_48") (pintype "bidirectional"))
      (node (ref "U1") (pin "64") (pinfunction "VDD3_64") (pintype "bidirectional"))
      (node (ref "U20") (pin "8") (pinfunction "VCC_8") (pintype "power_in"))
      (node (ref "U21") (pin "8") (pinfunction "VCC_8") (pintype "power_in"))
    )
    (net (code "2") (name "+3V0_ANALOG") (class "Default")
      (node (ref "C13") (pin "2") (pinfunction "2_2") (pintype "passive"))
      (node (ref "C14") (pin "2") (pinfunction "2_2") (pintype "passive"))
      (node (ref "C16") (pin "2") (pinfunction "2_2") (pintype "passive"))
      (node (ref "C18") (pin "2") (pinfunction "2_2") (pintype "passive"))
      (node (ref "C27") (pin "2") (pinfunction "2_2") (pintype "passive"))
      (node (ref "C33") (pin "2") (pinfunction "2_2") (pintype "passive"))
      (node (ref "C34") (pin "2") (pinfunction "2_2") (pintype "passive"))
      (node (ref "C36") (pin "2") (pinfunction "2_2") (pintype "passive"))
      (node (ref "C37") (pin "2") (pinfunction "2_2") (pintype "passive"))
      (node (ref "C42") (pin "2") (pinfunction "2_2") (pintype "passive"))
      (node (ref "C51") (pin "1") (pinfunction "1_1") (pintype "passive"))
      (node (ref "C53") (pin "1") (pinfunction "1_1") (pintype "passive"))
      (node (ref "L10") (pin "1") (pinfunction "1_1") (pintype "bidirectional"))
      (node (ref "U10") (pin "4") (pinfunction "VDD_4") (pintype "power_in"))
      (node (ref "U11") (pin "4") (pinfunction "VDD_4") (pintype "power_in"))
      (node (ref "U12") (pin "2") (pinfunction "VCC_2") (pintype "power_in"))
      (node (ref "U12") (pin "6") (pinfunction "PON_6") (pintype "input"))
      (node (ref "U13") (pin "2") (pinfunction "VCC_2") (pintype "power_in"))
      (node (ref "U13") (pin "6") (pinfunction "PON_6") (pintype "input"))
      (node (ref "U15") (pin "4") (pinfunction "VDD_4") (pintype "power_in"))
      (node (ref "U16") (pin "2") (pinfunction "VCC_2") (pintype "power_in"))
      (node (ref "U16") (pin "6") (pinfunction "PON_6") (pintype "input"))
      (node (ref "U18") (pin "2") (pinfunction "VCC_2") (pintype "power_in"))
      (node (ref "U18") (pin "6") (pinfunction "PON_6") (pintype "input"))
      (node (ref "U19") (pin "4") (pinfunction "VDD_4") (pintype "power_in"))
      (node (ref "U2") (pin "4") (pinfunction "VDD_4") (pintype "power_in"))
      (node (ref "U20") (pin "2") (pinfunction "~{SHDN}_2") (pintype "input"))
      (node (ref "U21") (pin "2") (pinfunction "~{SHDN}_2") (pintype "input"))
      (node (ref "U22") (pin "1") (pinfunction "OUT_1") (pintype "power_in"))
      (node (ref "U3") (pin "4") (pinfunction "VDD_4") (pintype "power_in"))
      (node (ref "U4") (pin "4") (pinfunction "VDD_4") (pintype "power_in"))
      (node (ref "U9") (pin "4") (pinfunction "VDD_4") (pintype "power_in"))
    )
    (net (code "3") (name "+3V0_DIGITAL") (class "Default")
      (node (ref "C56") (pin "1") (pinfunction "1_1") (pintype "passive"))
      (node (ref "C58") (pin "1") (pinfunction "1_1") (pintype "passive"))
      (node (ref "J1") (pin "3") (pinfunction "3_3") (pintype "passive"))
      (node (ref "L10") (pin "2") (pinfunction "2_2") (pintype "bidirectional"))
    )
    (net (code "4") (name "+3V3_ANALOG") (class "Default")
      (node (ref "C10") (pin "2") (pinfunction "2_2") (pintype "passive"))
      (node (ref "C11") (pin "2") (pinfunction "2_2") (pintype "passive"))
      (node (ref "C12") (pin "2") (pinfunction "2_2") (pintype "passive"))
      (node (ref "C7") (pin "2") (pinfunction "2_2") (pintype "passive"))
      (node (ref "C8") (pin "2") (pinfunction "2_2") (pintype "passive"))
      (node (ref "C9") (pin "2") (pinfunction "2_2") (pintype "passive"))
    )
    (net (code "5") (name "+5V0") (class "Default")
      (node (ref "C15") (pin "2") (pinfunction "2_2") (pintype "passive"))
      (node (ref "C17") (pin "2") (pinfunction "2_2") (pintype "passive"))
      (node (ref "C23") (pin "1") (pinfunction "1_1") (pintype "passive"))
      (node (ref "C24") (pin "1") (pinfunction "1_1") (pintype "passive"))
      (node (ref "C28") (pin "2") (pinfunction "2_2") (pintype "passive"))
      (node (ref "C29") (pin "2") (pinfunction "2_2") (pintype "passive"))
      (node (ref "C38") (pin "1") (pinfunction "1_1") (pintype "passive"))
      (node (ref "C39") (pin "1") (pinfunction "1_1") (pintype "passive"))
      (node (ref "C49") (pin "1") (pinfunction "1_1") (pintype "passive"))
      (node (ref "C55") (pin "1") (pinfunction "1_1") (pintype "passive"))
      (node (ref "C57") (pin "1") (pinfunction "1_1") (pintype "passive"))
      (node (ref "C59") (pin "1") (pinfunction "1_1") (pintype "passive"))
      (node (ref "J1") (pin "1") (pinfunction "1_1") (pintype "passive"))
      (node (ref "L1") (pin "1") (pinfunction "1_1") (pintype "bidirectional"))
      (node (ref "L11") (pin "2") (pinfunction "2_2") (pintype "bidirectional"))
      (node (ref "L3") (pin "2") (pinfunction "2_2") (pintype "bidirectional"))
      (node (ref "L5") (pin "1") (pinfunction "1_1") (pintype "bidirectional"))
      (node (ref "L7") (pin "2") (pinfunction "2_2") (pintype "bidirectional"))
      (node (ref "U14") (pin "12") (pinfunction "VDD_12") (pintype "bidirectional"))
      (node (ref "U17") (pin "12") (pinfunction "VDD_12") (pintype "bidirectional"))
      (node (ref "U22") (pin "4") (pinfunction "EN_4") (pintype "input"))
      (node (ref "U22") (pin "6") (pinfunction "IN_6") (pintype "power_in"))
    )
    (net (code "6") (name "BAND_SWITCH") (class "Default")
      (node (ref "J1") (pin "9") (pinfunction "9_9") (pintype "passive"))
      (node (ref "R2") (pin "2") (pinfunction "2_2") (pintype "passive"))
      (node (ref "U1") (pin "16") (pinfunction "PA2_16") (pintype "bidirectional"))
      (node (ref "U10") (pin "6") (pinfunction "CTRL_6") (pintype "input"))
      (node (ref "U11") (pin "6") (pinfunction "CTRL_6") (pintype "input"))
      (node (ref "U2") (pin "6") (pinfunction "CTRL_6") (pintype "input"))
      (node (ref "U3") (pin "6") (pinfunction "CTRL_6") (pintype "input"))
      (node (ref "U4") (pin "6") (pinfunction "CTRL_6") (pintype "input"))
      (node (ref "U9") (pin "6") (pinfunction "CTRL_6") (pintype "input"))
    )
    (net (code "7") (name "CELL_ANT") (class "Default")
      (node (ref "U11") (pin "5") (pinfunction "RFIN_5") (pintype "bidirectional"))
      (node (ref "X2") (pin "ANTENNA") (pinfunction "ANT_ANTENNA") (pintype "bidirectional"))
    )
    (net (code "8") (name "GND") (class "Default")
      (node (ref "C1") (pin "1") (pinfunction "1_1") (pintype "passive"))
      (node (ref "C10") (pin "1") (pinfunction "1_1") (pintype "passive"))
      (node (ref "C11") (pin "1") (pinfunction "1_1") (pintype "passive"))
      (node (ref "C12") (pin "1") (pinfunction "1_1") (pintype "passive"))
      (node (ref "C13") (pin "1") (pinfunction "1_1") (pintype "passive"))
      (node (ref "C14") (pin "1") (pinfunction "1_1") (pintype "passive"))
      (node (ref "C15") (pin "1") (pinfunction "1_1") (pintype "passive"))
      (node (ref "C16") (pin "1") (pinfunction "1_1") (pintype "passive"))
      (node (ref "C17") (pin "1") (pinfunction "1_1") (pintype "passive"))
      (node (ref "C18") (pin "1") (pinfunction "1_1") (pintype "passive"))
      (node (ref "C2") (pin "2") (pinfunction "2_2") (pintype "passive"))
      (node (ref "C22") (pin "2") (pinfunction "2_2") (pintype "passive"))
      (node (ref "C23") (pin "2") (pinfunction "2_2") (pintype "passive"))
      (node (ref "C24") (pin "2") (pinfunction "2_2") (pintype "passive"))
      (node (ref "C26") (pin "2") (pinfunction "2_2") (pintype "passive"))
      (node (ref "C27") (pin "1") (pinfunction "1_1") (pintype "passive"))
      (node (ref "C28") (pin "1") (pinfunction "1_1") (pintype "passive"))
      (node (ref "C29") (pin "1") (pinfunction "1_1") (pintype "passive"))
      (node (ref "C3") (pin "2") (pinfunction "2_2") (pintype "passive"))
      (node (ref "C33") (pin "1") (pinfunction "1_1") (pintype "passive"))
      (node (ref "C34") (pin "1") (pinfunction "1_1") (pintype "passive"))
      (node (ref "C35") (pin "2") (pinfunction "2_2") (pintype "passive"))
      (node (ref "C36") (pin "1") (pinfunction "1_1") (pintype "passive"))
      (node (ref "C37") (pin "1") (pinfunction "1_1") (pintype "passive"))
      (node (ref "C38") (pin "2") (pinfunction "2_2") (pintype "passive"))
      (node (ref "C39") (pin "2") (pinfunction "2_2") (pintype "passive"))
      (node (ref "C4") (pin "1") (pinfunction "1_1") (pintype "passive"))
      (node (ref "C41") (pin "2") (pinfunction "2_2") (pintype "passive"))
      (node (ref "C42") (pin "1") (pinfunction "1_1") (pintype "passive"))
      (node (ref "C43") (pin "2") (pinfunction "2_2") (pintype "passive"))
      (node (ref "C44") (pin "2") (pinfunction "2_2") (pintype "passive"))
      (node (ref "C45") (pin "2") (pinfunction "2_2") (pintype "passive"))
      (node (ref "C46") (pin "2") (pinfunction "2_2") (pintype "passive"))
      (node (ref "C47") (pin "2") (pinfunction "2_2") (pintype "passive"))
      (node (ref "C48") (pin "2") (pinfunction "2_2") (pintype "passive"))
      (node (ref "C49") (pin "2") (pinfunction "2_2") (pintype "passive"))
      (node (ref "C5") (pin "2") (pinfunction "2_2") (pintype "passive"))
      (node (ref "C50") (pin "2") (pinfunction "2_2") (pintype "passive"))
      (node (ref "C51") (pin "2") (pinfunction "2_2") (pintype "passive"))
      (node (ref "C52") (pin "2") (pinfunction "2_2") (pintype "passive"))
      (node (ref "C53") (pin "2") (pinfunction "2_2") (pintype "passive"))
      (node (ref "C54") (pin "2") (pinfunction "2_2") (pintype "passive"))
      (node (ref "C55") (pin "2") (pinfunction "2_2") (pintype "passive"))
      (node (ref "C56") (pin "2") (pinfunction "2_2") (pintype "passive"))
      (node (ref "C57") (pin "2") (pinfunction "2_2") (pintype "passive"))
      (node (ref "C58") (pin "2") (pinfunction "2_2") (pintype "passive"))
      (node (ref "C59") (pin "2") (pinfunction "2_2") (pintype "passive"))
      (node (ref "C6") (pin "1") (pinfunction "1_1") (pintype "passive"))
      (node (ref "C7") (pin "1") (pinfunction "1_1") (pintype "passive"))
      (node (ref "C8") (pin "1") (pinfunction "1_1") (pintype "passive"))
      (node (ref "C9") (pin "1") (pinfunction "1_1") (pintype "passive"))
      (node (ref "HY1") (pin "P$2") (pinfunction "GND_P$2") (pintype "bidirectional"))
      (node (ref "HY1") (pin "P$5") (pinfunction "GND_P$5") (pintype "bidirectional"))
      (node (ref "HY2") (pin "P$2") (pinfunction "GND_P$2") (pintype "bidirectional"))
      (node (ref "HY2") (pin "P$5") (pinfunction "GND_P$5") (pintype "bidirectional"))
      (node (ref "IC1") (pin "4") (pinfunction "PGND_4") (pintype "power_in"))
      (node (ref "IC1") (pin "9") (pinfunction "GND_9") (pintype "power_in"))
      (node (ref "IC1") (pin "PP") (pinfunction "PP_PP") (pintype "power_in"))
      (node (ref "IC1") (pin "PP@1") (pinfunction "PP_PP@1") (pintype "power_in"))
      (node (ref "IC1") (pin "PP@2") (pinfunction "PP_PP@2") (pintype "power_in"))
      (node (ref "J1") (pin "10") (pinfunction "10_10") (pintype "passive"))
      (node (ref "J1") (pin "4") (pinfunction "4_4") (pintype "passive"))
      (node (ref "J1") (pin "7") (pinfunction "7_7") (pintype "passive"))
      (node (ref "R1") (pin "1") (pinfunction "1_1") (pintype "passive"))
      (node (ref "R10") (pin "2") (pinfunction "2_2") (pintype "passive"))
      (node (ref "R11") (pin "2") (pinfunction "2_2") (pintype "passive"))
      (node (ref "R2") (pin "1") (pinfunction "1_1") (pintype "passive"))
      (node (ref "R3") (pin "2") (pinfunction "2_2") (pintype "passive"))
      (node (ref "R4") (pin "2") (pinfunction "2_2") (pintype "passive"))
      (node (ref "R5") (pin "2") (pinfunction "2_2") (pintype "passive"))
      (node (ref "R8") (pin "2") (pinfunction "2_2") (pintype "passive"))
      (node (ref "R9") (pin "2") (pinfunction "2_2") (pintype "passive"))
      (node (ref "S1") (pin "P$3") (pinfunction "P$3_P$3") (pintype "bidirectional"))
      (node (ref "U1") (pin "12") (pinfunction "VSSA/VREF-_12") (pintype "bidirectional"))
      (node (ref "U1") (pin "18") (pinfunction "VSS1_18") (pintype "bidirectional"))
      (node (ref "U1") (pin "31") (pinfunction "VSS2_31") (pintype "bidirectional"))
      (node (ref "U1") (pin "47") (pinfunction "VSS3_47") (pintype "bidirectional"))
      (node (ref "U1") (pin "63") (pinfunction "VSS4_63") (pintype "bidirectional"))
      (node (ref "U10") (pin "2") (pinfunction "GND_2") (pintype "power_in"))
      (node (ref "U11") (pin "2") (pinfunction "GND_2") (pintype "power_in"))
      (node (ref "U12") (pin "1") (pinfunction "GND_1") (pintype "power_in"))
      (node (ref "U12") (pin "4") (pinfunction "GND_4") (pintype "power_in"))
      (node (ref "U13") (pin "1") (pinfunction "GND_1") (pintype "power_in"))
      (node (ref "U13") (pin "4") (pinfunction "GND_4") (pintype "power_in"))
      (node (ref "U14") (pin "25") (pinfunction "GND_25") (pintype "bidirectional"))
      (node (ref "U15") (pin "2") (pinfunction "GND_2") (pintype "power_in"))
      (node (ref "U16") (pin "1") (pinfunction "GND_1") (pintype "power_in"))
      (node (ref "U16") (pin "4") (pinfunction "GND_4") (pintype "power_in"))
      (node (ref "U17") (pin "25") (pinfunction "GND_25") (pintype "bidirectional"))
      (node (ref "U18") (pin "1") (pinfunction "GND_1") (pintype "power_in"))
      (node (ref "U18") (pin "4") (pinfunction "GND_4") (pintype "power_in"))
      (node (ref "U19") (pin "2") (pinfunction "GND_2") (pintype "power_in"))
      (node (ref "U2") (pin "2") (pinfunction "GND_2") (pintype "power_in"))
      (node (ref "U20") (pin "3") (pinfunction "GND_2_3") (pintype "power_in"))
      (node (ref "U20") (pin "5") (pinfunction "GND_5") (pintype "power_in"))
      (node (ref "U21") (pin "3") (pinfunction "GND_2_3") (pintype "power_in"))
      (node (ref "U21") (pin "5") (pinfunction "GND_5") (pintype "power_in"))
      (node (ref "U22") (pin "5") (pinfunction "GND_5") (pintype "power_in"))
      (node (ref "U22") (pin "7") (pinfunction "PAD_7") (pintype "power_in"))
      (node (ref "U3") (pin "2") (pinfunction "GND_2") (pintype "power_in"))
      (node (ref "U4") (pin "2") (pinfunction "GND_2") (pintype "power_in"))
      (node (ref "U5") (pin "2") (pinfunction "GND_2") (pintype "bidirectional"))
      (node (ref "U5") (pin "4") (pinfunction "GND_4") (pintype "bidirectional"))
      (node (ref "U5") (pin "5") (pinfunction "GND_5") (pintype "bidirectional"))
      (node (ref "U5") (pin "7") (pinfunction "GND_7") (pintype "bidirectional"))
      (node (ref "U5") (pin "8") (pinfunction "GND_8") (pintype "bidirectional"))
      (node (ref "U6") (pin "2") (pinfunction "GND_2") (pintype "bidirectional"))
      (node (ref "U6") (pin "4") (pinfunction "GND_4") (pintype "bidirectional"))
      (node (ref "U6") (pin "5") (pinfunction "GND_5") (pintype "bidirectional"))
      (node (ref "U6") (pin "7") (pinfunction "GND_7") (pintype "bidirectional"))
      (node (ref "U6") (pin "8") (pinfunction "GND_8") (pintype "bidirectional"))
      (node (ref "U7") (pin "2") (pinfunction "GND_2") (pintype "bidirectional"))
      (node (ref "U7") (pin "4") (pinfunction "GND_4") (pintype "bidirectional"))
      (node (ref "U7") (pin "5") (pinfunction "GND_5") (pintype "bidirectional"))
      (node (ref "U7") (pin "7") (pinfunction "GND_7") (pintype "bidirectional"))
      (node (ref "U7") (pin "8") (pinfunction "GND_8") (pintype "bidirectional"))
      (node (ref "U8") (pin "2") (pinfunction "GND_2") (pintype "bidirectional"))
      (node (ref "U8") (pin "4") (pinfunction "GND_4") (pintype "bidirectional"))
      (node (ref "U8") (pin "5") (pinfunction "GND_5") (pintype "bidirectional"))
      (node (ref "U8") (pin "7") (pinfunction "GND_7") (pintype "bidirectional"))
      (node (ref "U8") (pin "8") (pinfunction "GND_8") (pintype "bidirectional"))
      (node (ref "U9") (pin "2") (pinfunction "GND_2") (pintype "power_in"))
      (node (ref "X1") (pin "GND1") (pinfunction "GND1_GND1") (pintype "power_in"))
      (node (ref "X1") (pin "GND2") (pinfunction "GND2_GND2") (pintype "power_in"))
      (node (ref "X1") (pin "GND3") (pinfunction "GND3_GND3") (pintype "power_in"))
      (node (ref "X1") (pin "GND4") (pinfunction "GND4_GND4") (pintype "power_in"))
      (node (ref "X2") (pin "GND1") (pinfunction "GND1_GND1") (pintype "power_in"))
      (node (ref "X2") (pin "GND2") (pinfunction "GND2_GND2") (pintype "power_in"))
      (node (ref "X2") (pin "GND3") (pinfunction "GND3_GND3") (pintype "power_in"))
      (node (ref "X2") (pin "GND4") (pinfunction "GND4_GND4") (pintype "power_in"))
    )
    (net (code "9") (name "JTAG_RESET") (class "Default")
      (node (ref "S1") (pin "P$2") (pinfunction "P$2_P$2") (pintype "bidirectional"))
      (node (ref "U1") (pin "7") (pinfunction "NRST_7") (pintype "bidirectional"))
    )
    (net (code "10") (name "JTAG_SWCLK") (class "Default")
      (node (ref "U1") (pin "49") (pinfunction "PA14_49") (pintype "bidirectional"))
    )
    (net (code "11") (name "JTAG_SWDIO") (class "Default")
      (node (ref "U1") (pin "46") (pinfunction "PA13_46") (pintype "bidirectional"))
    )
    (net (code "12") (name "JTAG_SWO") (class "Default")
      (node (ref "U1") (pin "55") (pinfunction "PB3_55") (pintype "bidirectional"))
    )
    (net (code "13") (name "Net-(C25-Pad1)") (class "Default")
      (node (ref "C25") (pin "1") (pinfunction "1_1") (pintype "passive"))
      (node (ref "L4") (pin "2") (pinfunction "2_2") (pintype "bidirectional"))
    )
    (net (code "14") (name "Net-(C40-Pad1)") (class "Default")
      (node (ref "C40") (pin "1") (pinfunction "1_1") (pintype "passive"))
      (node (ref "L8") (pin "2") (pinfunction "2_2") (pintype "bidirectional"))
    )
    (net (code "15") (name "Net-(HY1-50)") (class "Default")
      (node (ref "HY1") (pin "P$4") (pinfunction "50_P$4") (pintype "bidirectional"))
      (node (ref "R8") (pin "1") (pinfunction "1_1") (pintype "passive"))
    )
    (net (code "16") (name "Net-(HY1-COUPLE)") (class "Default")
      (node (ref "HY1") (pin "P$6") (pinfunction "COUPLE_P$6") (pintype "bidirectional"))
      (node (ref "R10") (pin "1") (pinfunction "1_1") (pintype "passive"))
      (node (ref "U21") (pin "1") (pinfunction "RFIN_1") (pintype "input"))
    )
    (net (code "17") (name "Net-(HY2-50)") (class "Default")
      (node (ref "HY2") (pin "P$4") (pinfunction "50_P$4") (pintype "bidirectional"))
      (node (ref "R9") (pin "1") (pinfunction "1_1") (pintype "passive"))
    )
    (net (code "18") (name "Net-(HY2-COUPLE)") (class "Default")
      (node (ref "HY2") (pin "P$6") (pinfunction "COUPLE_P$6") (pintype "bidirectional"))
      (node (ref "R11") (pin "1") (pinfunction "1_1") (pintype "passive"))
      (node (ref "U20") (pin "1") (pinfunction "RFIN_1") (pintype "input"))
    )
    (net (code "19") (name "Net-(IC1-FB)") (class "Default")
      (node (ref "C54") (pin "1") (pinfunction "1_1") (pintype "passive"))
      (node (ref "IC1") (pin "10") (pinfunction "FB_10") (pintype "input"))
      (node (ref "IC1") (pin "2") (pinfunction "VOUT_2") (pintype "passive"))
      (node (ref "L11") (pin "1") (pinfunction "1_1") (pintype "bidirectional"))
    )
    (net (code "20") (name "Net-(IC1-L)") (class "Default")
      (node (ref "IC1") (pin "3") (pinfunction "L_3") (pintype "input"))
      (node (ref "L9") (pin "1") (pinfunction "1_1") (pintype "passive"))
    )
    (net (code "21") (name "Net-(IC1-VAUX)") (class "Default")
      (node (ref "C52") (pin "1") (pinfunction "1_1") (pintype "passive"))
      (node (ref "IC1") (pin "1") (pinfunction "VAUX_1") (pintype "bidirectional"))
    )
    (net (code "22") (name "Net-(L2-Pad1)") (class "Default")
      (node (ref "L2") (pin "1") (pinfunction "1_1") (pintype "bidirectional"))
      (node (ref "R6") (pin "1") (pinfunction "1_1") (pintype "passive"))
    )
    (net (code "23") (name "Net-(L6-Pad1)") (class "Default")
      (node (ref "L6") (pin "1") (pinfunction "1_1") (pintype "bidirectional"))
      (node (ref "R7") (pin "1") (pinfunction "1_1") (pintype "passive"))
    )
    (net (code "24") (name "Net-(LED1-PadC)") (class "Default")
      (node (ref "LED1") (pin "C") (pinfunction "C_C") (pintype "passive"))
      (node (ref "R4") (pin "1") (pinfunction "1_1") (pintype "passive"))
    )
    (net (code "25") (name "Net-(LED2-PadC)") (class "Default")
      (node (ref "LED2") (pin "C") (pinfunction "C_C") (pintype "passive"))
      (node (ref "R5") (pin "1") (pinfunction "1_1") (pintype "passive"))
    )
    (net (code "26") (name "Net-(U1-PA9)") (class "Default")
      (node (ref "LED2") (pin "A") (pinfunction "A_A") (pintype "passive"))
      (node (ref "U1") (pin "42") (pinfunction "PA9_42") (pintype "bidirectional"))
    )
    (net (code "27") (name "Net-(U1-PA10)") (class "Default")
      (node (ref "LED1") (pin "A") (pinfunction "A_A") (pintype "passive"))
      (node (ref "U1") (pin "43") (pinfunction "PA10_43") (pintype "bidirectional"))
    )
    (net (code "28") (name "Net-(U1-PH3-BOOT0)") (class "Default")
      (node (ref "R3") (pin "1") (pinfunction "1_1") (pintype "passive"))
      (node (ref "U1") (pin "60") (pinfunction "PH3-BOOT0_60") (pintype "bidirectional"))
    )
    (net (code "29") (name "Net-(U1-VBAT)") (class "Default")
      (node (ref "C2") (pin "1") (pinfunction "1_1") (pintype "passive"))
      (node (ref "U1") (pin "1") (pinfunction "VBAT_1") (pintype "bidirectional"))
    )
    (net (code "30") (name "Net-(U2-RF1)") (class "Default")
      (node (ref "U2") (pin "3") (pinfunction "RF1_3") (pintype "bidirectional"))
      (node (ref "U5") (pin "6") (pinfunction "ANT_6") (pintype "bidirectional"))
    )
    (net (code "31") (name "Net-(U2-RF2)") (class "Default")
      (node (ref "U2") (pin "1") (pinfunction "RF2_1") (pintype "bidirectional"))
      (node (ref "U6") (pin "6") (pinfunction "ANT_6") (pintype "bidirectional"))
    )
    (net (code "32") (name "Net-(U3-RF1)") (class "Default")
      (node (ref "U3") (pin "3") (pinfunction "RF1_3") (pintype "bidirectional"))
      (node (ref "U7") (pin "3") (pinfunction "TX_3") (pintype "bidirectional"))
    )
    (net (code "33") (name "Net-(U3-RF2)") (class "Default")
      (node (ref "U3") (pin "1") (pinfunction "RF2_1") (pintype "bidirectional"))
      (node (ref "U8") (pin "3") (pinfunction "TX_3") (pintype "bidirectional"))
    )
    (net (code "34") (name "Net-(U4-RF1)") (class "Default")
      (node (ref "U4") (pin "3") (pinfunction "RF1_3") (pintype "bidirectional"))
      (node (ref "U7") (pin "1") (pinfunction "RX_1") (pintype "bidirectional"))
    )
    (net (code "35") (name "Net-(U4-RF2)") (class "Default")
      (node (ref "U4") (pin "1") (pinfunction "RF2_1") (pintype "bidirectional"))
      (node (ref "U8") (pin "1") (pinfunction "RX_1") (pintype "bidirectional"))
    )
    (net (code "36") (name "Net-(U5-TX)") (class "Default")
      (node (ref "U5") (pin "3") (pinfunction "TX_3") (pintype "bidirectional"))
      (node (ref "U9") (pin "3") (pinfunction "RF1_3") (pintype "bidirectional"))
    )
    (net (code "37") (name "Net-(U6-TX)") (class "Default")
      (node (ref "U6") (pin "3") (pinfunction "TX_3") (pintype "bidirectional"))
      (node (ref "U9") (pin "1") (pinfunction "RF2_1") (pintype "bidirectional"))
    )
    (net (code "38") (name "Net-(U10-RF1)") (class "Default")
      (node (ref "U10") (pin "3") (pinfunction "RF1_3") (pintype "bidirectional"))
      (node (ref "U5") (pin "1") (pinfunction "RX_1") (pintype "bidirectional"))
    )
    (net (code "39") (name "Net-(U10-RF2)") (class "Default")
      (node (ref "U10") (pin "1") (pinfunction "RF2_1") (pintype "bidirectional"))
      (node (ref "U6") (pin "1") (pinfunction "RX_1") (pintype "bidirectional"))
    )
    (net (code "40") (name "Net-(U11-RF1)") (class "Default")
      (node (ref "U11") (pin "3") (pinfunction "RF1_3") (pintype "bidirectional"))
      (node (ref "U7") (pin "6") (pinfunction "ANT_6") (pintype "bidirectional"))
    )
    (net (code "41") (name "Net-(U11-RF2)") (class "Default")
      (node (ref "U11") (pin "1") (pinfunction "RF2_1") (pintype "bidirectional"))
      (node (ref "U8") (pin "6") (pinfunction "ANT_6") (pintype "bidirectional"))
    )
    (net (code "42") (name "Net-(U12-AO)") (class "Default")
      (node (ref "U12") (pin "3") (pinfunction "AO_3") (pintype "output"))
      (node (ref "U13") (pin "5") (pinfunction "AI_5") (pintype "input"))
    )
    (net (code "43") (name "Net-(U13-AO)") (class "Default")
      (node (ref "C21") (pin "1") (pinfunction "1_1") (pintype "passive"))
      (node (ref "U13") (pin "3") (pinfunction "AO_3") (pintype "output"))
    )
    (net (code "44") (name "Net-(U14-AMP1_IN)") (class "Default")
      (node (ref "C21") (pin "2") (pinfunction "2_2") (pintype "passive"))
      (node (ref "U14") (pin "8") (pinfunction "AMP1_IN_8") (pintype "bidirectional"))
    )
    (net (code "45") (name "Net-(U14-AMP1_OUT{slash}VCC)") (class "Default")
      (node (ref "C19") (pin "1") (pinfunction "1_1") (pintype "passive"))
      (node (ref "L1") (pin "2") (pinfunction "2_2") (pintype "bidirectional"))
      (node (ref "U14") (pin "5") (pinfunction "AMP1_OUT/VCC_5") (pintype "bidirectional"))
    )
    (net (code "46") (name "Net-(U14-AMP2_IN)") (class "Default")
      (node (ref "R6") (pin "2") (pinfunction "2_2") (pintype "passive"))
      (node (ref "U14") (pin "20") (pinfunction "AMP2_IN_20") (pintype "bidirectional"))
    )
    (net (code "47") (name "Net-(U14-AMP2_OUT{slash}VCC)") (class "Default")
      (node (ref "L3") (pin "1") (pinfunction "1_1") (pintype "bidirectional"))
      (node (ref "L4") (pin "1") (pinfunction "1_1") (pintype "bidirectional"))
      (node (ref "U14") (pin "16") (pinfunction "AMP2_OUT/VCC_16") (pintype "bidirectional"))
    )
    (net (code "48") (name "Net-(U14-DSA_IN)") (class "Default")
      (node (ref "C19") (pin "2") (pinfunction "2_2") (pintype "passive"))
      (node (ref "U14") (pin "3") (pinfunction "DSA_IN_3") (pintype "bidirectional"))
    )
    (net (code "49") (name "Net-(U14-DSA_OUT)") (class "Default")
      (node (ref "C20") (pin "2") (pinfunction "2_2") (pintype "passive"))
      (node (ref "U14") (pin "23") (pinfunction "DSA_OUT_23") (pintype "bidirectional"))
    )
    (net (code "50") (name "Net-(U15-RF1)") (class "Default")
      (node (ref "U15") (pin "3") (pinfunction "RF1_3") (pintype "bidirectional"))
      (node (ref "U16") (pin "3") (pinfunction "AO_3") (pintype "output"))
    )
    (net (code "51") (name "Net-(U15-RF2)") (class "Default")
      (node (ref "U15") (pin "1") (pinfunction "RF2_1") (pintype "bidirectional"))
      (node (ref "U19") (pin "1") (pinfunction "RF2_1") (pintype "bidirectional"))
    )
    (net (code "52") (name "Net-(U15-RFIN)") (class "Default")
      (node (ref "C32") (pin "1") (pinfunction "1_1") (pintype "passive"))
      (node (ref "U15") (pin "5") (pinfunction "RFIN_5") (pintype "bidirectional"))
    )
    (net (code "53") (name "Net-(U16-AI)") (class "Default")
      (node (ref "U16") (pin "5") (pinfunction "AI_5") (pintype "input"))
      (node (ref "U18") (pin "3") (pinfunction "AO_3") (pintype "output"))
    )
    (net (code "54") (name "Net-(U17-AMP1_IN)") (class "Default")
      (node (ref "C32") (pin "2") (pinfunction "2_2") (pintype "passive"))
      (node (ref "U17") (pin "8") (pinfunction "AMP1_IN_8") (pintype "bidirectional"))
    )
    (net (code "55") (name "Net-(U17-AMP1_OUT{slash}VCC)") (class "Default")
      (node (ref "C30") (pin "1") (pinfunction "1_1") (pintype "passive"))
      (node (ref "L5") (pin "2") (pinfunction "2_2") (pintype "bidirectional"))
      (node (ref "U17") (pin "5") (pinfunction "AMP1_OUT/VCC_5") (pintype "bidirectional"))
    )
    (net (code "56") (name "Net-(U17-AMP2_IN)") (class "Default")
      (node (ref "R7") (pin "2") (pinfunction "2_2") (pintype "passive"))
      (node (ref "U17") (pin "20") (pinfunction "AMP2_IN_20") (pintype "bidirectional"))
    )
    (net (code "57") (name "Net-(U17-AMP2_OUT{slash}VCC)") (class "Default")
      (node (ref "L7") (pin "1") (pinfunction "1_1") (pintype "bidirectional"))
      (node (ref "L8") (pin "1") (pinfunction "1_1") (pintype "bidirectional"))
      (node (ref "U17") (pin "16") (pinfunction "AMP2_OUT/VCC_16") (pintype "bidirectional"))
    )
    (net (code "58") (name "Net-(U17-DSA_IN)") (class "Default")
      (node (ref "C30") (pin "2") (pinfunction "2_2") (pintype "passive"))
      (node (ref "U17") (pin "3") (pinfunction "DSA_IN_3") (pintype "bidirectional"))
    )
    (net (code "59") (name "Net-(U17-DSA_OUT)") (class "Default")
      (node (ref "C31") (pin "2") (pinfunction "2_2") (pintype "passive"))
      (node (ref "U17") (pin "23") (pinfunction "DSA_OUT_23") (pintype "bidirectional"))
    )
    (net (code "60") (name "Net-(U18-AI)") (class "Default")
      (node (ref "U18") (pin "5") (pinfunction "AI_5") (pintype "input"))
      (node (ref "U19") (pin "3") (pinfunction "RF1_3") (pintype "bidirectional"))
    )
    (net (code "61") (name "Net-(U20-CLPF)") (class "Default")
      (node (ref "C43") (pin "1") (pinfunction "1_1") (pintype "passive"))
      (node (ref "U20") (pin "4") (pinfunction "CLPF_4") (pintype "passive"))
    )
    (net (code "62") (name "Net-(U21-CLPF)") (class "Default")
      (node (ref "C44") (pin "1") (pinfunction "1_1") (pintype "passive"))
      (node (ref "U21") (pin "4") (pinfunction "CLPF_4") (pintype "passive"))
    )
    (net (code "63") (name "POWER+") (class "Default")
      (node (ref "C50") (pin "1") (pinfunction "1_1") (pintype "passive"))
      (node (ref "IC1") (pin "5") (pinfunction "VIN_5") (pintype "input"))
      (node (ref "IC1") (pin "6") (pinfunction "EN_6") (pintype "input"))
      (node (ref "IC1") (pin "7") (pinfunction "UVLO_7") (pintype "input"))
      (node (ref "IC1") (pin "8") (pinfunction "PS_8") (pintype "input"))
      (node (ref "L9") (pin "2") (pinfunction "2_2") (pintype "passive"))
    )
    (net (code "64") (name "PWR_ADC1") (class "Default")
      (node (ref "J1") (pin "5") (pinfunction "5_5") (pintype "passive"))
      (node (ref "U1") (pin "8") (pinfunction "PC0_8") (pintype "bidirectional"))
      (node (ref "U20") (pin "7") (pinfunction "OUT_7") (pintype "output"))
    )
    (net (code "65") (name "PWR_ADC2") (class "Default")
      (node (ref "J1") (pin "6") (pinfunction "6_6") (pintype "passive"))
      (node (ref "U1") (pin "9") (pinfunction "PC1_9") (pintype "bidirectional"))
      (node (ref "U21") (pin "7") (pinfunction "OUT_7") (pintype "output"))
    )
    (net (code "66") (name "RX_DIRECTIONAL_COUPLER") (class "Default")
      (node (ref "C25") (pin "2") (pinfunction "2_2") (pintype "passive"))
      (node (ref "C26") (pin "1") (pinfunction "1_1") (pintype "passive"))
      (node (ref "HY1") (pin "P$1") (pinfunction "IN_P$1") (pintype "bidirectional"))
    )
    (net (code "67") (name "RX_DSA_OUT") (class "Default")
      (node (ref "C20") (pin "1") (pinfunction "1_1") (pintype "passive"))
      (node (ref "C22") (pin "1") (pinfunction "1_1") (pintype "passive"))
      (node (ref "L2") (pin "2") (pinfunction "2_2") (pintype "bidirectional"))
    )
    (net (code "68") (name "RX_PATH_CELL") (class "Default")
      (node (ref "HY1") (pin "P$3") (pinfunction "OUT_P$3") (pintype "bidirectional"))
      (node (ref "U4") (pin "5") (pinfunction "RFIN_5") (pintype "bidirectional"))
    )
    (net (code "69") (name "RX_PATH_TOWER") (class "Default")
      (node (ref "U10") (pin "5") (pinfunction "RFIN_5") (pintype "bidirectional"))
      (node (ref "U12") (pin "5") (pinfunction "AI_5") (pintype "input"))
    )
    (net (code "70") (name "SPI1_CS1") (class "Default")
      (node (ref "U1") (pin "24") (pinfunction "PC4_24") (pintype "bidirectional"))
      (node (ref "U14") (pin "15") (pinfunction "LE_15") (pintype "bidirectional"))
    )
    (net (code "71") (name "SPI1_CS2") (class "Default")
      (node (ref "U1") (pin "25") (pinfunction "PC5_25") (pintype "bidirectional"))
      (node (ref "U17") (pin "15") (pinfunction "LE_15") (pintype "bidirectional"))
    )
    (net (code "72") (name "SPI1_MISO") (class "Default")
      (node (ref "U1") (pin "22") (pinfunction "PA6_22") (pintype "bidirectional"))
      (node (ref "U14") (pin "10") (pinfunction "SOD_10") (pintype "bidirectional"))
      (node (ref "U17") (pin "10") (pinfunction "SOD_10") (pintype "bidirectional"))
    )
    (net (code "73") (name "SPI1_MOSI") (class "Default")
      (node (ref "U1") (pin "23") (pinfunction "PA7_23") (pintype "bidirectional"))
      (node (ref "U14") (pin "14") (pinfunction "DATA_14") (pintype "bidirectional"))
      (node (ref "U17") (pin "14") (pinfunction "DATA_14") (pintype "bidirectional"))
    )
    (net (code "74") (name "SPI1_SCK") (class "Default")
      (node (ref "U1") (pin "21") (pinfunction "PA5_21") (pintype "bidirectional"))
      (node (ref "U14") (pin "13") (pinfunction "CLK_13") (pintype "bidirectional"))
      (node (ref "U17") (pin "13") (pinfunction "CLK_13") (pintype "bidirectional"))
    )
    (net (code "75") (name "TOWER_ANT") (class "Default")
      (node (ref "U2") (pin "5") (pinfunction "RFIN_5") (pintype "bidirectional"))
      (node (ref "X1") (pin "ANTENNA") (pinfunction "ANT_ANTENNA") (pintype "bidirectional"))
    )
    (net (code "76") (name "TX_DIRECTIONAL_COUPLER") (class "Default")
      (node (ref "C40") (pin "2") (pinfunction "2_2") (pintype "passive"))
      (node (ref "C41") (pin "1") (pinfunction "1_1") (pintype "passive"))
      (node (ref "HY2") (pin "P$1") (pinfunction "IN_P$1") (pintype "bidirectional"))
    )
    (net (code "77") (name "TX_DSA_OUT") (class "Default")
      (node (ref "C31") (pin "1") (pinfunction "1_1") (pintype "passive"))
      (node (ref "C35") (pin "1") (pinfunction "1_1") (pintype "passive"))
      (node (ref "L6") (pin "2") (pinfunction "2_2") (pintype "bidirectional"))
    )
    (net (code "78") (name "TX_LNA_BYPASS") (class "Default")
      (node (ref "J1") (pin "8") (pinfunction "8_8") (pintype "passive"))
      (node (ref "R1") (pin "2") (pinfunction "2_2") (pintype "passive"))
      (node (ref "U1") (pin "15") (pinfunction "PA1_15") (pintype "bidirectional"))
      (node (ref "U15") (pin "6") (pinfunction "CTRL_6") (pintype "input"))
      (node (ref "U19") (pin "6") (pinfunction "CTRL_6") (pintype "input"))
    )
    (net (code "79") (name "TX_PATH_CELL") (class "Default")
      (node (ref "U19") (pin "5") (pinfunction "RFIN_5") (pintype "bidirectional"))
      (node (ref "U3") (pin "5") (pinfunction "RFIN_5") (pintype "bidirectional"))
    )
    (net (code "80") (name "TX_PATH_TOWER") (class "Default")
      (node (ref "HY2") (pin "P$3") (pinfunction "OUT_P$3") (pintype "bidirectional"))
      (node (ref "U9") (pin "5") (pinfunction "RFIN_5") (pintype "bidirectional"))
    )
    (net (code "81") (name "VDD") (class "Default")
      (node (ref "J2") (pin "2") (pinfunction "VDD_2") (pintype "power_in"))
    )
    (net (code "82") (name "VSS(GND)") (class "Default")
      (node (ref "J2") (pin "3") (pinfunction "VSS(GND)_3") (pintype "power_in"))
    )
    (net (code "83") (name "unconnected-(J2-ICSP_CLK{slash}PGC-Pad5)") (class "Default")
      (node (ref "J2") (pin "5") (pinfunction "ICSP_CLK/PGC_5") (pintype "output"))
    )
    (net (code "84") (name "unconnected-(J2-ICSP_DAT{slash}PGD-Pad4)") (class "Default")
      (node (ref "J2") (pin "4") (pinfunction "ICSP_DAT/PGD_4") (pintype "bidirectional"))
    )
    (net (code "85") (name "unconnected-(J2-LVP-Pad6)") (class "Default")
      (node (ref "J2") (pin "6") (pinfunction "LVP_6") (pintype "bidirectional"))
    )
    (net (code "86") (name "unconnected-(J2-VPP{slash}MCLR-Pad1)") (class "Default")
      (node (ref "J2") (pin "1") (pinfunction "VPP/MCLR_1") (pintype "passive"))
    )
    (net (code "87") (name "unconnected-(S1-PadP$1)") (class "Default")
      (node (ref "S1") (pin "P$1") (pinfunction "P$1_P$1") (pintype "bidirectional"))
    )
    (net (code "88") (name "unconnected-(S1-PadP$4)") (class "Default")
      (node (ref "S1") (pin "P$4") (pinfunction "P$4_P$4") (pintype "bidirectional"))
    )
    (net (code "89") (name "unconnected-(U1-PA0-Pad14)") (class "Default")
      (node (ref "U1") (pin "14") (pinfunction "PA0_14") (pintype "bidirectional"))
    )
    (net (code "90") (name "unconnected-(U1-PA3-Pad17)") (class "Default")
      (node (ref "U1") (pin "17") (pinfunction "PA3_17") (pintype "bidirectional"))
    )
    (net (code "91") (name "unconnected-(U1-PA4-Pad20)") (class "Default")
      (node (ref "U1") (pin "20") (pinfunction "PA4_20") (pintype "bidirectional"))
    )
    (net (code "92") (name "unconnected-(U1-PA8-Pad41)") (class "Default")
      (node (ref "U1") (pin "41") (pinfunction "PA8_41") (pintype "bidirectional"))
    )
    (net (code "93") (name "unconnected-(U1-PA11-Pad44)") (class "Default")
      (node (ref "U1") (pin "44") (pinfunction "PA11_44") (pintype "bidirectional"))
    )
    (net (code "94") (name "unconnected-(U1-PA12-Pad45)") (class "Default")
      (node (ref "U1") (pin "45") (pinfunction "PA12_45") (pintype "bidirectional"))
    )
    (net (code "95") (name "unconnected-(U1-PA15-Pad50)") (class "Default")
      (node (ref "U1") (pin "50") (pinfunction "PA15_50") (pintype "bidirectional"))
    )
    (net (code "96") (name "unconnected-(U1-PB0-Pad26)") (class "Default")
      (node (ref "U1") (pin "26") (pinfunction "PB0_26") (pintype "bidirectional"))
    )
    (net (code "97") (name "unconnected-(U1-PB1-Pad27)") (class "Default")
      (node (ref "U1") (pin "27") (pinfunction "PB1_27") (pintype "bidirectional"))
    )
    (net (code "98") (name "unconnected-(U1-PB2-Pad28)") (class "Default")
      (node (ref "U1") (pin "28") (pinfunction "PB2_28") (pintype "bidirectional"))
    )
    (net (code "99") (name "unconnected-(U1-PB4-Pad56)") (class "Default")
      (node (ref "U1") (pin "56") (pinfunction "PB4_56") (pintype "bidirectional"))
    )
    (net (code "100") (name "unconnected-(U1-PB5-Pad57)") (class "Default")
      (node (ref "U1") (pin "57") (pinfunction "PB5_57") (pintype "bidirectional"))
    )
    (net (code "101") (name "unconnected-(U1-PB6-Pad58)") (class "Default")
      (node (ref "U1") (pin "58") (pinfunction "PB6_58") (pintype "bidirectional"))
    )
    (net (code "102") (name "unconnected-(U1-PB7-Pad59)") (class "Default")
      (node (ref "U1") (pin "59") (pinfunction "PB7_59") (pintype "bidirectional"))
    )
    (net (code "103") (name "unconnected-(U1-PB8-Pad61)") (class "Default")
      (node (ref "U1") (pin "61") (pinfunction "PB8_61") (pintype "bidirectional"))
    )
    (net (code "104") (name "unconnected-(U1-PB9-Pad62)") (class "Default")
      (node (ref "U1") (pin "62") (pinfunction "PB9_62") (pintype "bidirectional"))
    )
    (net (code "105") (name "unconnected-(U1-PB10-Pad29)") (class "Default")
      (node (ref "U1") (pin "29") (pinfunction "PB10_29") (pintype "bidirectional"))
    )
    (net (code "106") (name "unconnected-(U1-PB11-Pad30)") (class "Default")
      (node (ref "U1") (pin "30") (pinfunction "PB11_30") (pintype "bidirectional"))
    )
    (net (code "107") (name "unconnected-(U1-PB12-Pad33)") (class "Default")
      (node (ref "U1") (pin "33") (pinfunction "PB12_33") (pintype "bidirectional"))
    )
    (net (code "108") (name "unconnected-(U1-PB13-Pad34)") (class "Default")
      (node (ref "U1") (pin "34") (pinfunction "PB13_34") (pintype "bidirectional"))
    )
    (net (code "109") (name "unconnected-(U1-PB14-Pad35)") (class "Default")
      (node (ref "U1") (pin "35") (pinfunction "PB14_35") (pintype "bidirectional"))
    )
    (net (code "110") (name "unconnected-(U1-PB15-Pad36)") (class "Default")
      (node (ref "U1") (pin "36") (pinfunction "PB15_36") (pintype "bidirectional"))
    )
    (net (code "111") (name "unconnected-(U1-PC2-Pad10)") (class "Default")
      (node (ref "U1") (pin "10") (pinfunction "PC2_10") (pintype "bidirectional"))
    )
    (net (code "112") (name "unconnected-(U1-PC3-Pad11)") (class "Default")
      (node (ref "U1") (pin "11") (pinfunction "PC3_11") (pintype "bidirectional"))
    )
    (net (code "113") (name "unconnected-(U1-PC6-Pad37)") (class "Default")
      (node (ref "U1") (pin "37") (pinfunction "PC6_37") (pintype "bidirectional"))
    )
    (net (code "114") (name "unconnected-(U1-PC7-Pad38)") (class "Default")
      (node (ref "U1") (pin "38") (pinfunction "PC7_38") (pintype "bidirectional"))
    )
    (net (code "115") (name "unconnected-(U1-PC8-Pad39)") (class "Default")
      (node (ref "U1") (pin "39") (pinfunction "PC8_39") (pintype "bidirectional"))
    )
    (net (code "116") (name "unconnected-(U1-PC9-Pad40)") (class "Default")
      (node (ref "U1") (pin "40") (pinfunction "PC9_40") (pintype "bidirectional"))
    )
    (net (code "117") (name "unconnected-(U1-PC10-Pad51)") (class "Default")
      (node (ref "U1") (pin "51") (pinfunction "PC10_51") (pintype "bidirectional"))
    )
    (net (code "118") (name "unconnected-(U1-PC11-Pad52)") (class "Default")
      (node (ref "U1") (pin "52") (pinfunction "PC11_52") (pintype "bidirectional"))
    )
    (net (code "119") (name "unconnected-(U1-PC12-Pad53)") (class "Default")
      (node (ref "U1") (pin "53") (pinfunction "PC12_53") (pintype "bidirectional"))
    )
    (net (code "120") (name "unconnected-(U1-PC13-Pad2)") (class "Default")
      (node (ref "U1") (pin "2") (pinfunction "PC13_2") (pintype "bidirectional"))
    )
    (net (code "121") (name "unconnected-(U1-PC14-OSC32_IN-Pad3)") (class "Default")
      (node (ref "U1") (pin "3") (pinfunction "PC14-OSC32_IN_3") (pintype "bidirectional"))
    )
    (net (code "122") (name "unconnected-(U1-PC15-OSC32_OUT-Pad4)") (class "Default")
      (node (ref "U1") (pin "4") (pinfunction "PC15-OSC32_OUT_4") (pintype "bidirectional"))
    )
    (net (code "123") (name "unconnected-(U1-PD2-Pad54)") (class "Default")
      (node (ref "U1") (pin "54") (pinfunction "PD2_54") (pintype "bidirectional"))
    )
    (net (code "124") (name "unconnected-(U1-PH0-OSC_IN-Pad5)") (class "Default")
      (node (ref "U1") (pin "5") (pinfunction "PH0-OSC_IN_5") (pintype "bidirectional"))
    )
    (net (code "125") (name "unconnected-(U1-PH1-OSC_OUT-Pad6)") (class "Default")
      (node (ref "U1") (pin "6") (pinfunction "PH1-OSC_OUT_6") (pintype "bidirectional"))
    )
    (net (code "126") (name "unconnected-(U20-NC-Pad6)") (class "Default")
      (node (ref "U20") (pin "6") (pinfunction "NC_6") (pintype "no_connect"))
    )
    (net (code "127") (name "unconnected-(U21-NC-Pad6)") (class "Default")
      (node (ref "U21") (pin "6") (pinfunction "NC_6") (pintype "no_connect"))
    )
    (net (code "128") (name "unconnected-(U22-NC-Pad2)") (class "Default")
      (node (ref "U22") (pin "2") (pinfunction "NC_2") (pintype "passive"))
    )
    (net (code "129") (name "unconnected-(U22-PG-Pad3)") (class "Default")
      (node (ref "U22") (pin "3") (pinfunction "PG_3") (pintype "output"))
    )
  )
)
